# duckypad.net
KiCad netlist of a schematic drawn in EAGLE
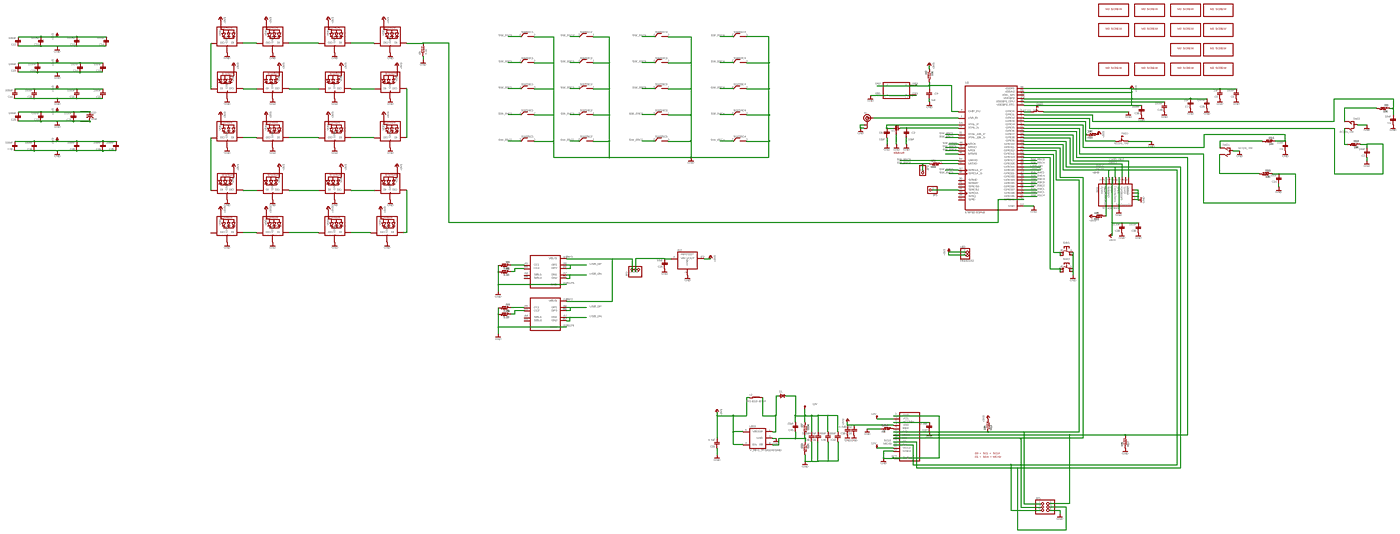
[diagram p0: schematic, sheet 1, overview]
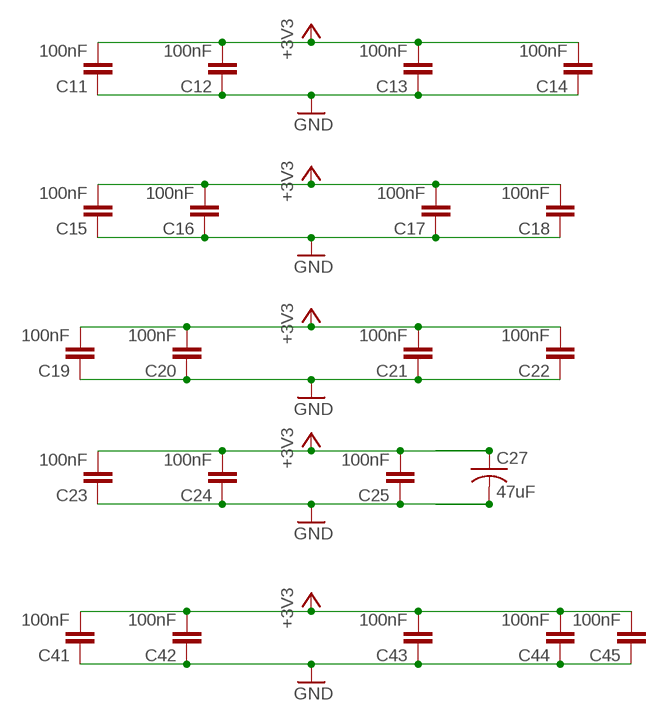
[diagram p1: schematic, sheet 1, part 1 of 4]
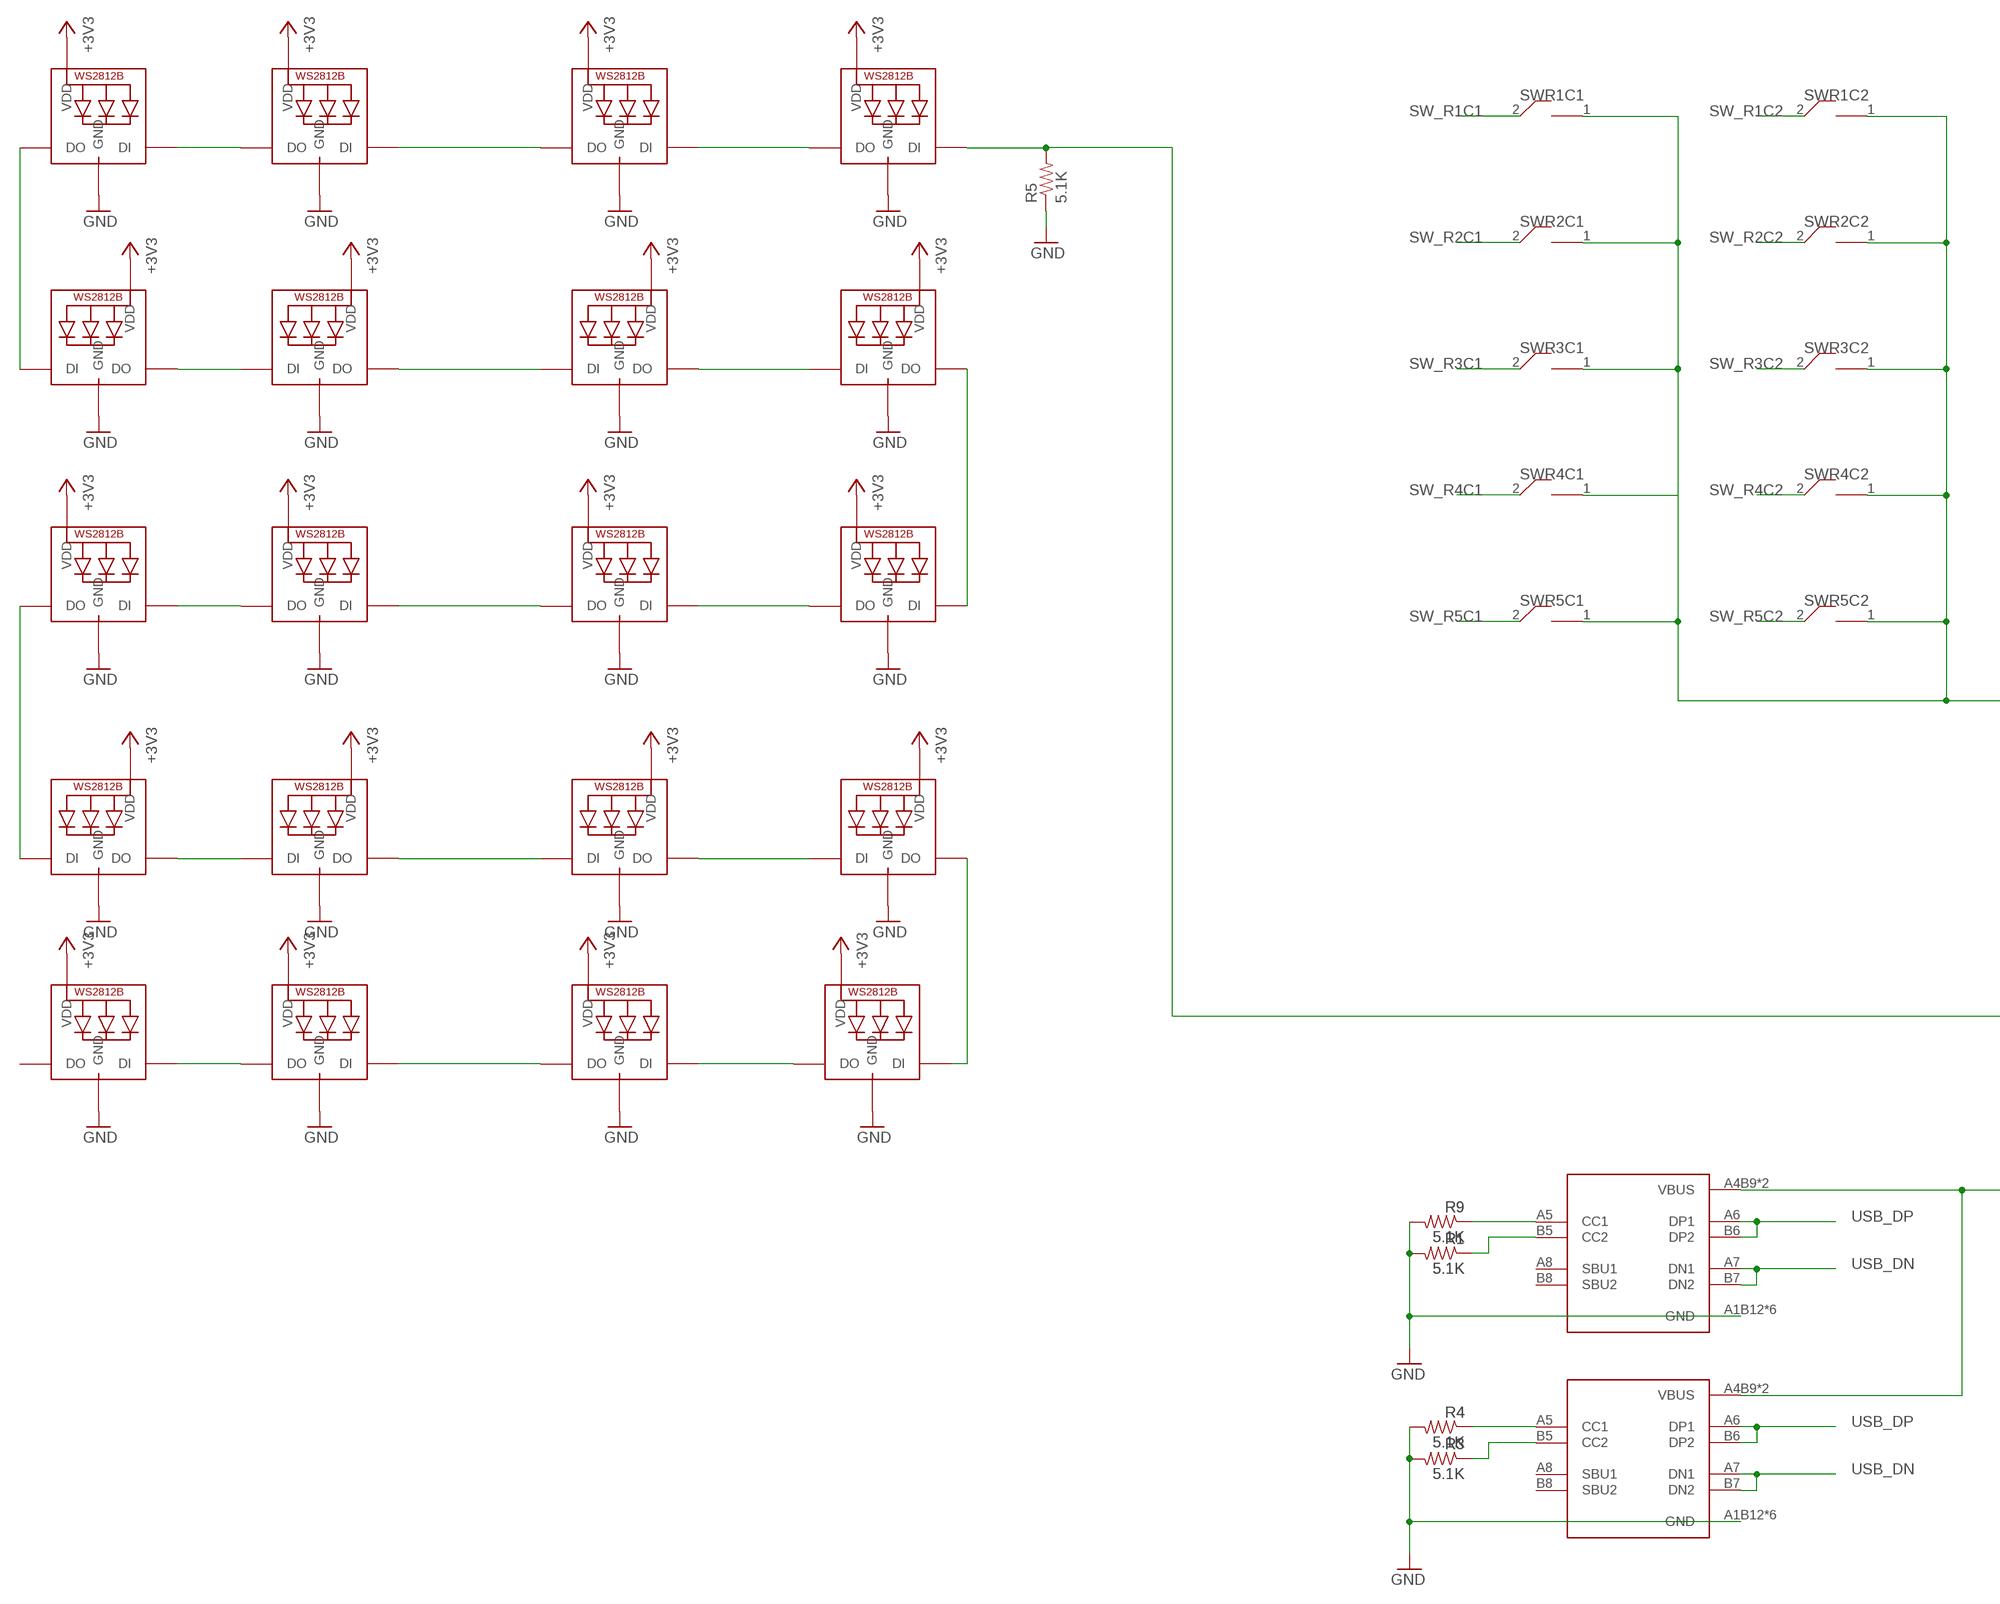
[diagram p2: schematic, sheet 1, part 2 of 4]
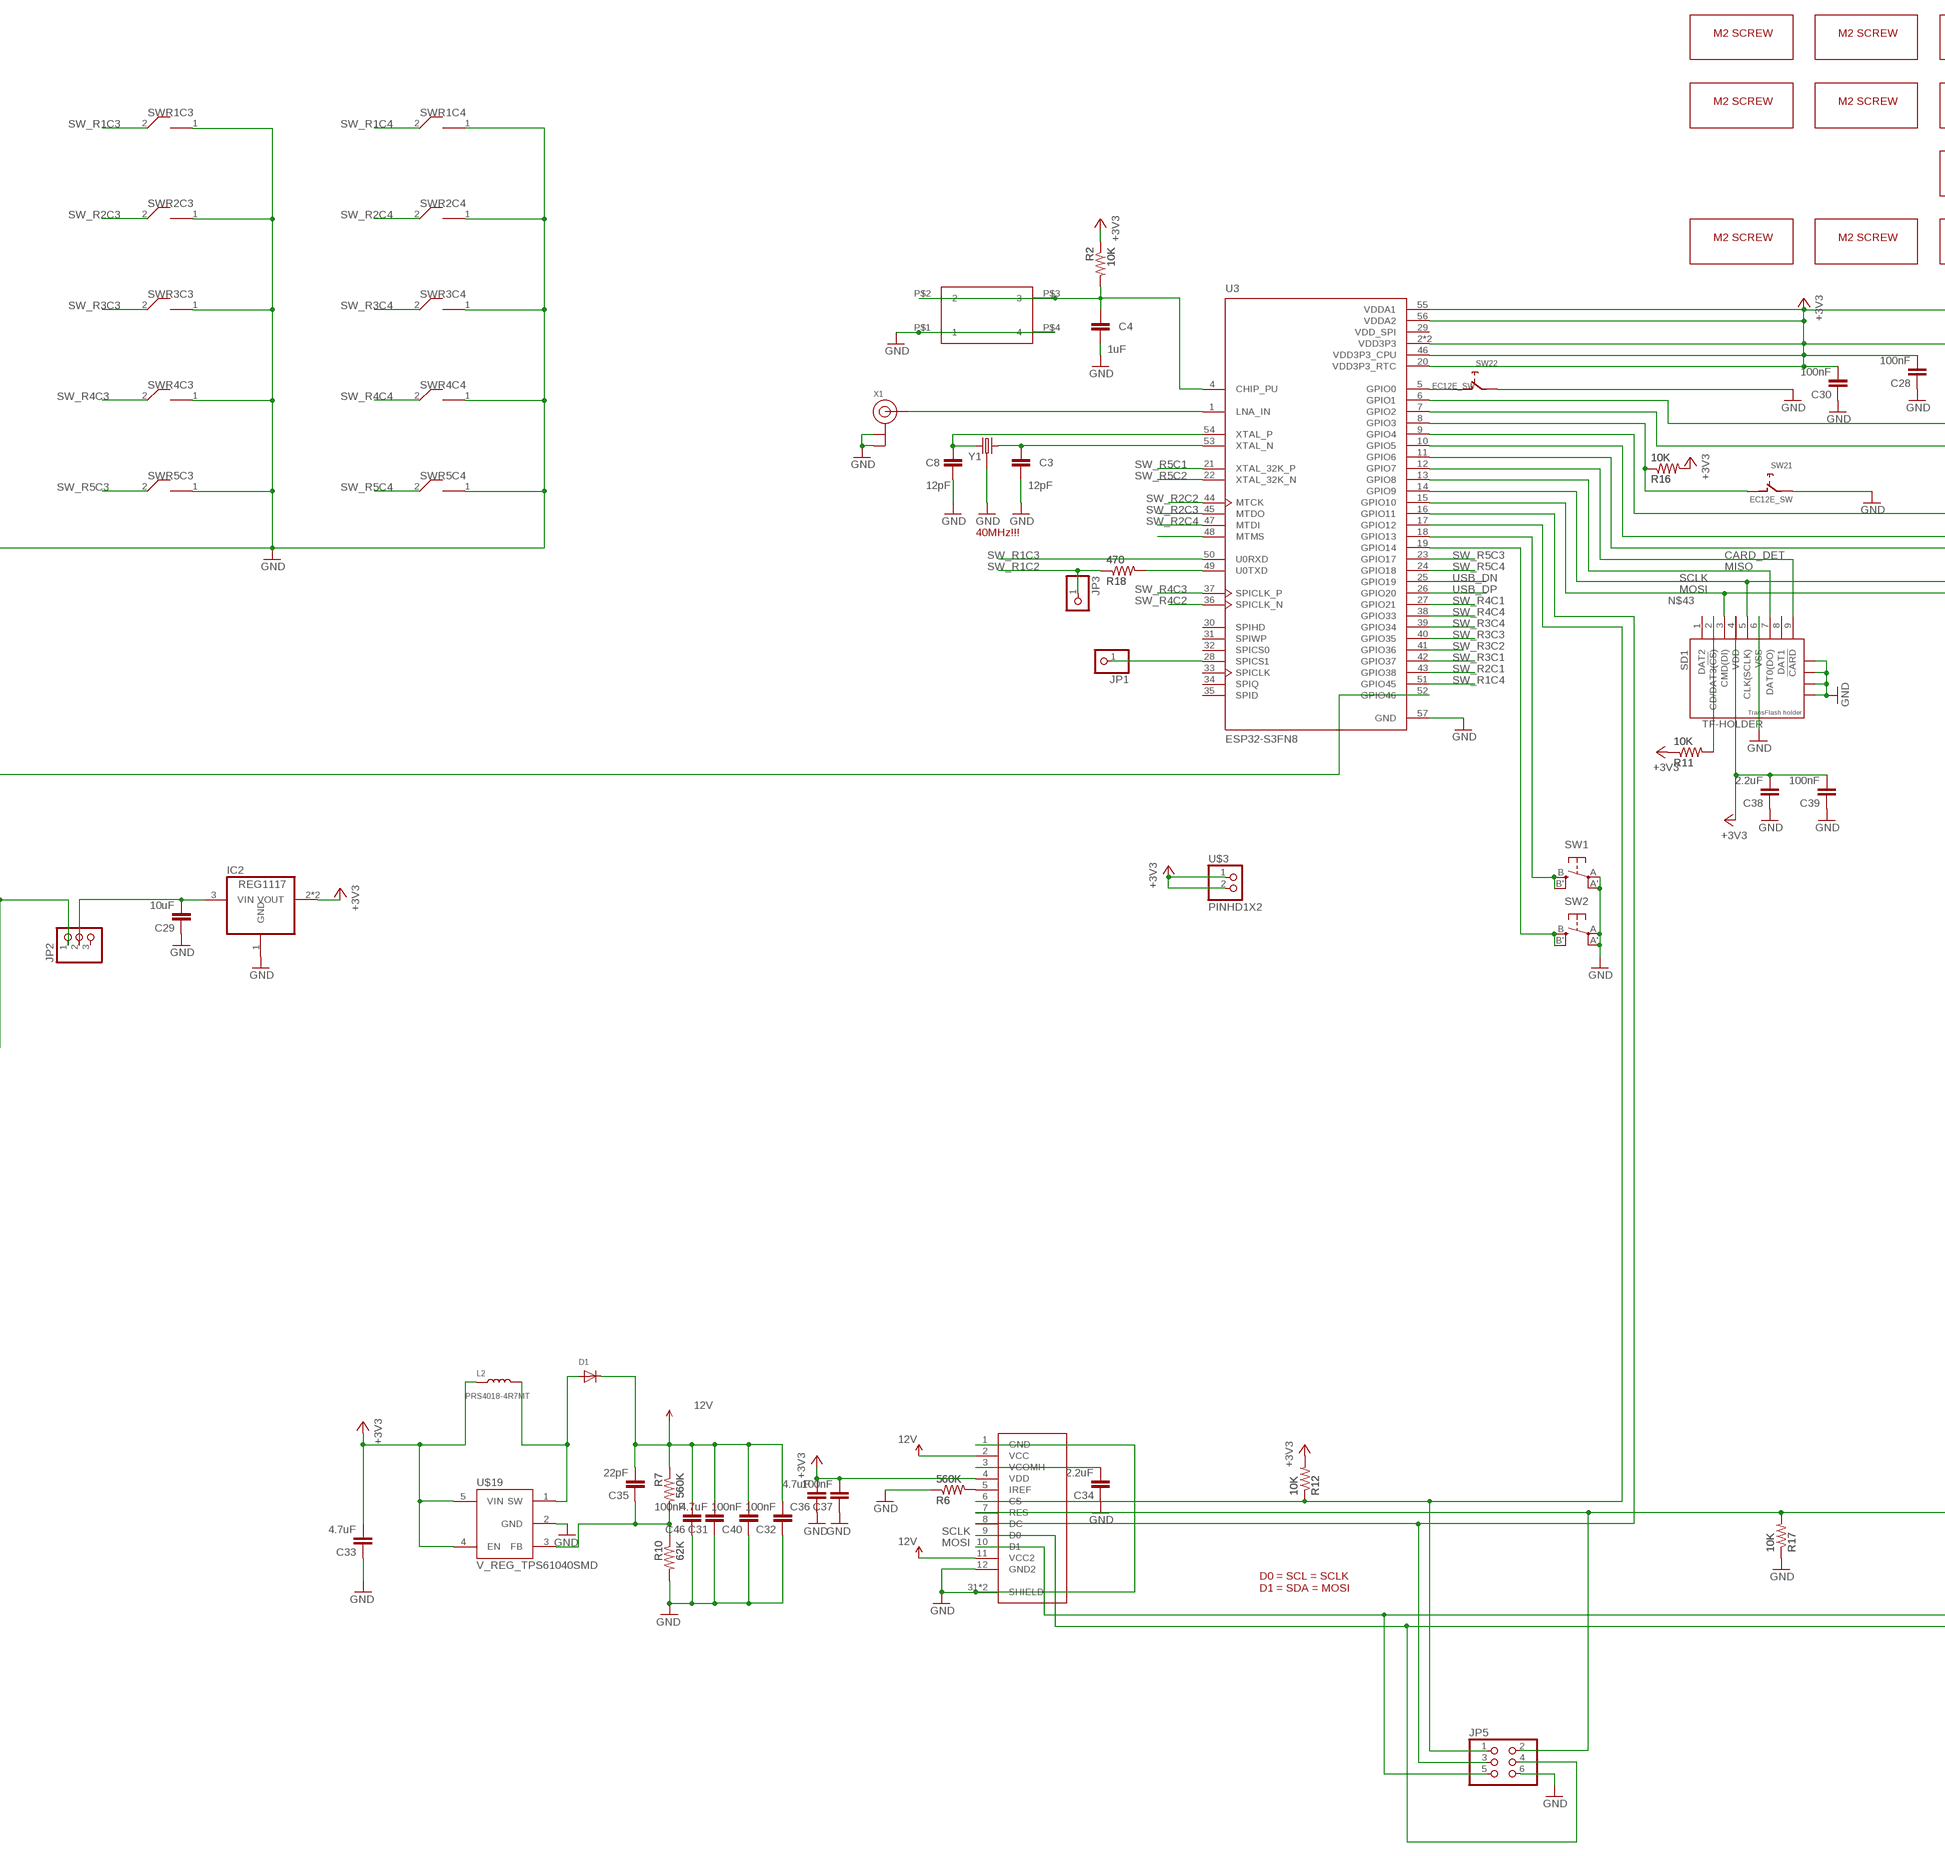
[diagram p3: schematic, sheet 1, part 3 of 4]
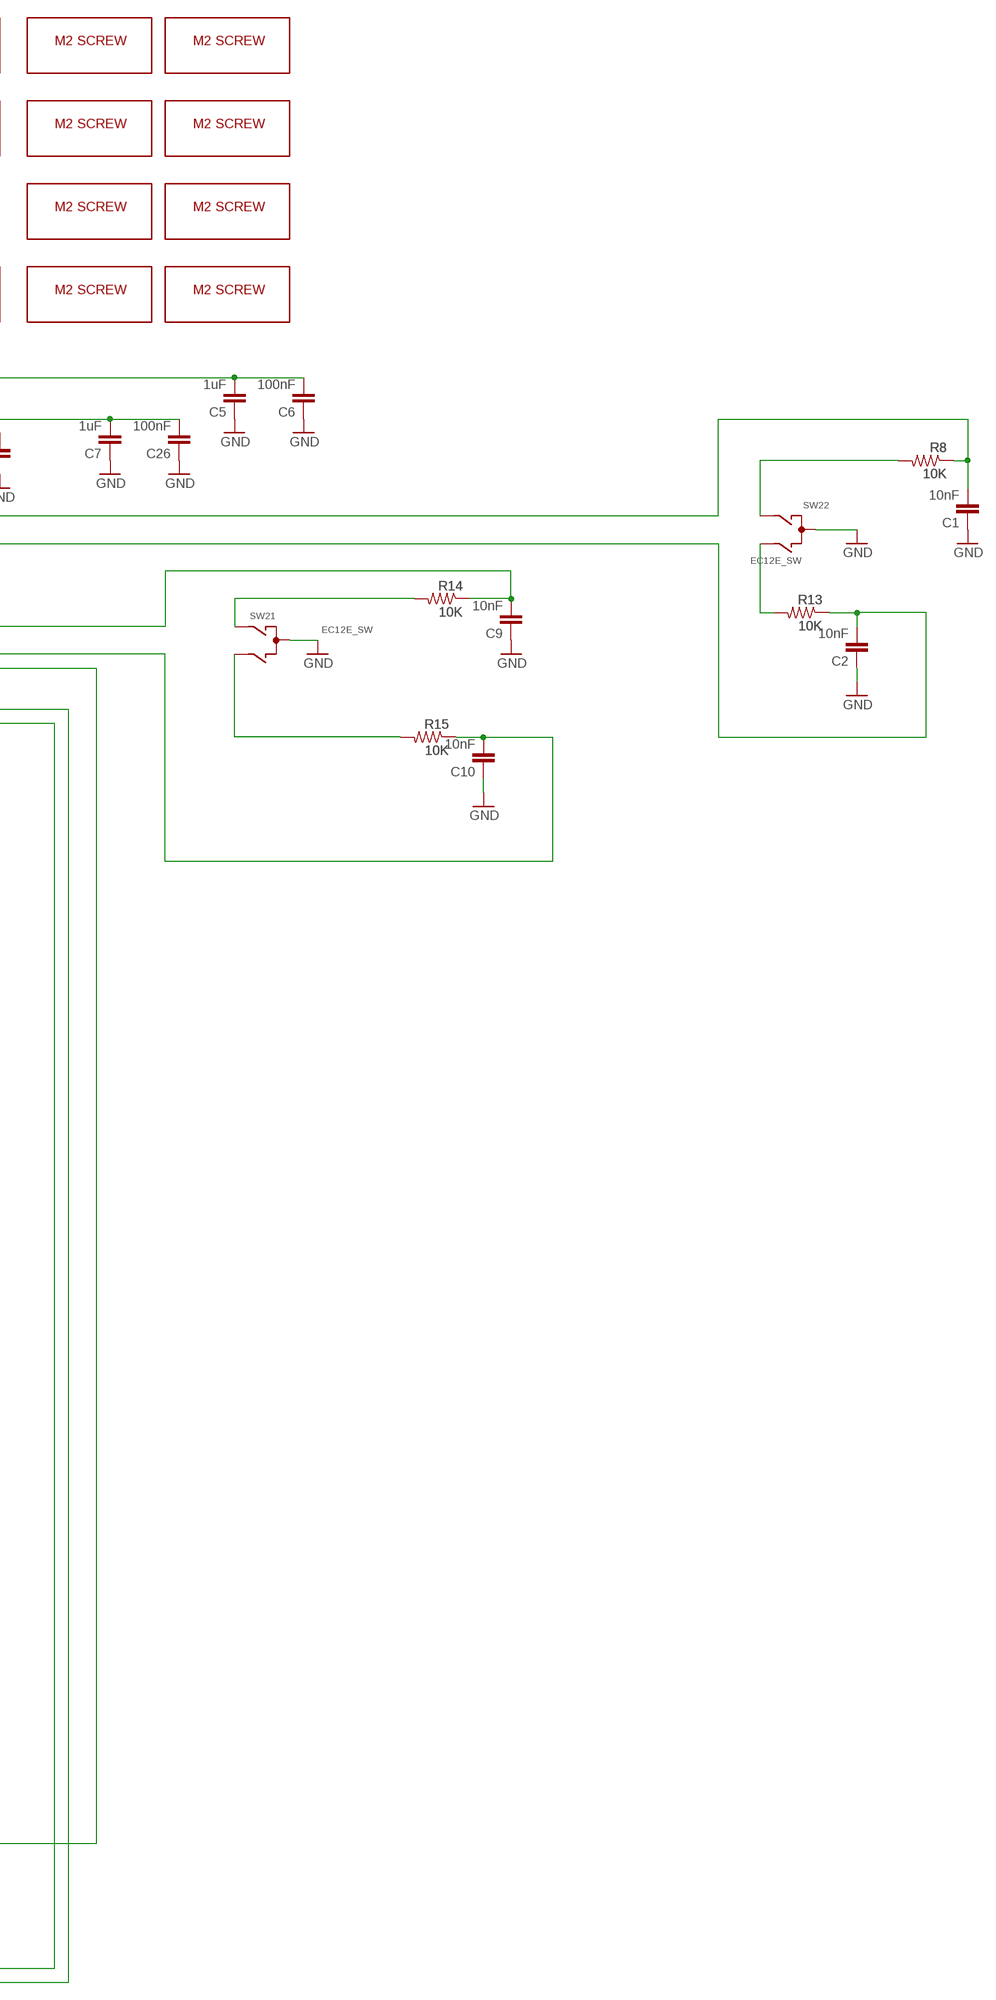
[diagram p4: schematic, sheet 1, part 4 of 4]

(export (version "E")
  (design (tool "Eeschema 10.0.6"))
  (components
    (comp (ref "C1")
      (value "10nF")
      (footprint "eagle-import:0805")
      (libsource (lib "eagle-import") (part "CAP0805"))
    )
    (comp (ref "C2")
      (value "10nF")
      (footprint "eagle-import:0805")
      (libsource (lib "eagle-import") (part "CAP0805"))
    )
    (comp (ref "C3")
      (value "12pF")
      (footprint "eagle-import:0805")
      (libsource (lib "eagle-import") (part "CAP0805"))
    )
    (comp (ref "C4")
      (value "1uF")
      (footprint "eagle-import:0805")
      (libsource (lib "eagle-import") (part "CAP0805"))
    )
    (comp (ref "C5")
      (value "1uF")
      (footprint "eagle-import:0805")
      (libsource (lib "eagle-import") (part "CAP0805"))
    )
    (comp (ref "C6")
      (value "100nF")
      (footprint "eagle-import:0805")
      (libsource (lib "eagle-import") (part "CAP0805"))
    )
    (comp (ref "C7")
      (value "1uF")
      (footprint "eagle-import:0805")
      (libsource (lib "eagle-import") (part "CAP0805"))
    )
    (comp (ref "C8")
      (value "12pF")
      (footprint "eagle-import:0805")
      (libsource (lib "eagle-import") (part "CAP0805"))
    )
    (comp (ref "C9")
      (value "10nF")
      (footprint "eagle-import:0805")
      (libsource (lib "eagle-import") (part "CAP0805"))
    )
    (comp (ref "C10")
      (value "10nF")
      (footprint "eagle-import:0805")
      (libsource (lib "eagle-import") (part "CAP0805"))
    )
    (comp (ref "C11")
      (value "100nF")
      (footprint "eagle-import:0805")
      (libsource (lib "eagle-import") (part "CAP0805"))
    )
    (comp (ref "C12")
      (value "100nF")
      (footprint "eagle-import:0805")
      (libsource (lib "eagle-import") (part "CAP0805"))
    )
    (comp (ref "C13")
      (value "100nF")
      (footprint "eagle-import:0805")
      (libsource (lib "eagle-import") (part "CAP0805"))
    )
    (comp (ref "C14")
      (value "100nF")
      (footprint "eagle-import:0805")
      (libsource (lib "eagle-import") (part "CAP0805"))
    )
    (comp (ref "C15")
      (value "100nF")
      (footprint "eagle-import:0805")
      (libsource (lib "eagle-import") (part "CAP0805"))
    )
    (comp (ref "C16")
      (value "100nF")
      (footprint "eagle-import:0805")
      (libsource (lib "eagle-import") (part "CAP0805"))
    )
    (comp (ref "C17")
      (value "100nF")
      (footprint "eagle-import:0805")
      (libsource (lib "eagle-import") (part "CAP0805"))
    )
    (comp (ref "C18")
      (value "100nF")
      (footprint "eagle-import:0805")
      (libsource (lib "eagle-import") (part "CAP0805"))
    )
    (comp (ref "C19")
      (value "100nF")
      (footprint "eagle-import:0805")
      (libsource (lib "eagle-import") (part "CAP0805"))
    )
    (comp (ref "C20")
      (value "100nF")
      (footprint "eagle-import:0805")
      (libsource (lib "eagle-import") (part "CAP0805"))
    )
    (comp (ref "C21")
      (value "100nF")
      (footprint "eagle-import:0805")
      (libsource (lib "eagle-import") (part "CAP0805"))
    )
    (comp (ref "C22")
      (value "100nF")
      (footprint "eagle-import:0805")
      (libsource (lib "eagle-import") (part "CAP0805"))
    )
    (comp (ref "C23")
      (value "100nF")
      (footprint "eagle-import:0805")
      (libsource (lib "eagle-import") (part "CAP0805"))
    )
    (comp (ref "C24")
      (value "100nF")
      (footprint "eagle-import:0805")
      (libsource (lib "eagle-import") (part "CAP0805"))
    )
    (comp (ref "C25")
      (value "100nF")
      (footprint "eagle-import:0805")
      (libsource (lib "eagle-import") (part "CAP0805"))
    )
    (comp (ref "C26")
      (value "100nF")
      (footprint "eagle-import:0805")
      (libsource (lib "eagle-import") (part "CAP0805"))
    )
    (comp (ref "C27")
      (value "47uF")
      (footprint "eagle-import:C1210")
      (libsource (lib "eagle-import") (part "C-USC1210"))
    )
    (comp (ref "C28")
      (value "100nF")
      (footprint "eagle-import:0805")
      (libsource (lib "eagle-import") (part "CAP0805"))
    )
    (comp (ref "C29")
      (value "10uF")
      (footprint "eagle-import:0805")
      (libsource (lib "eagle-import") (part "CAP0805"))
    )
    (comp (ref "C30")
      (value "100nF")
      (footprint "eagle-import:0805")
      (libsource (lib "eagle-import") (part "CAP0805"))
    )
    (comp (ref "C31")
      (value "4.7uF")
      (footprint "eagle-import:0805")
      (libsource (lib "eagle-import") (part "CAP0805"))
    )
    (comp (ref "C32")
      (value "100nF")
      (footprint "eagle-import:0805")
      (libsource (lib "eagle-import") (part "CAP0805"))
    )
    (comp (ref "C33")
      (value "4.7uF")
      (footprint "eagle-import:0805")
      (libsource (lib "eagle-import") (part "CAP0805"))
    )
    (comp (ref "C34")
      (value "2.2uF")
      (footprint "eagle-import:0805")
      (libsource (lib "eagle-import") (part "CAP0805"))
    )
    (comp (ref "C35")
      (value "22pF")
      (footprint "eagle-import:0805")
      (libsource (lib "eagle-import") (part "CAP0805"))
    )
    (comp (ref "C36")
      (value "4.7uF")
      (footprint "eagle-import:0805")
      (libsource (lib "eagle-import") (part "CAP0805"))
    )
    (comp (ref "C37")
      (value "100nF")
      (footprint "eagle-import:0805")
      (libsource (lib "eagle-import") (part "CAP0805"))
    )
    (comp (ref "C38")
      (value "2.2uF")
      (footprint "eagle-import:0805")
      (libsource (lib "eagle-import") (part "CAP0805"))
    )
    (comp (ref "C39")
      (value "100nF")
      (footprint "eagle-import:0805")
      (libsource (lib "eagle-import") (part "CAP0805"))
    )
    (comp (ref "C40")
      (value "100nF")
      (footprint "eagle-import:0805")
      (libsource (lib "eagle-import") (part "CAP0805"))
    )
    (comp (ref "C41")
      (value "100nF")
      (footprint "eagle-import:0805")
      (libsource (lib "eagle-import") (part "CAP0805"))
    )
    (comp (ref "C42")
      (value "100nF")
      (footprint "eagle-import:0805")
      (libsource (lib "eagle-import") (part "CAP0805"))
    )
    (comp (ref "C43")
      (value "100nF")
      (footprint "eagle-import:0805")
      (libsource (lib "eagle-import") (part "CAP0805"))
    )
    (comp (ref "C44")
      (value "100nF")
      (footprint "eagle-import:0805")
      (libsource (lib "eagle-import") (part "CAP0805"))
    )
    (comp (ref "C45")
      (value "100nF")
      (footprint "eagle-import:0805")
      (libsource (lib "eagle-import") (part "CAP0805"))
    )
    (comp (ref "C46")
      (value "100nF")
      (footprint "eagle-import:0805")
      (libsource (lib "eagle-import") (part "CAP0805"))
    )
    (comp (ref "D1")
      (value "DIODESOD-123")
      (footprint "eagle-import:SOD-123")
      (libsource (lib "eagle-import") (part "DIODESOD-123"))
    )
    (comp (ref "IC2")
      (value "REG1117")
      (footprint "eagle-import:SOT223")
      (libsource (lib "eagle-import") (part "REG1117"))
    )
    (comp (ref "JP1")
      (value "PINHD-1X1CB")
      (footprint "eagle-import:1X01-CLEANBIG")
      (libsource (lib "eagle-import") (part "PINHD-1X1CB"))
    )
    (comp (ref "JP2")
      (value "PINHD-1X3CB")
      (footprint "eagle-import:1X03-CLEANBIG")
      (libsource (lib "eagle-import") (part "PINHD-1X3CB"))
    )
    (comp (ref "JP3")
      (value "PINHD-1X1CB")
      (footprint "eagle-import:1X01-CLEANBIG")
      (libsource (lib "eagle-import") (part "PINHD-1X1CB"))
    )
    (comp (ref "JP5")
      (value "PINHD-2X3")
      (footprint "eagle-import:2X03")
      (libsource (lib "eagle-import") (part "PINHD-2X3"))
    )
    (comp (ref "L2")
      (value "PRS4018-4R7MT")
      (footprint "eagle-import:L4030")
      (libsource (lib "eagle-import") (part "L-4030"))
    )
    (comp (ref "LED_R1C1")
      (value "WS2812B")
      (footprint "eagle-import:REVERSE_MNT")
      (libsource (lib "eagle-import") (part "WS2812B"))
    )
    (comp (ref "LED_R1C2")
      (value "WS2812B")
      (footprint "eagle-import:REVERSE_MNT")
      (libsource (lib "eagle-import") (part "WS2812B"))
    )
    (comp (ref "LED_R1C3")
      (value "WS2812B")
      (footprint "eagle-import:REVERSE_MNT")
      (libsource (lib "eagle-import") (part "WS2812B"))
    )
    (comp (ref "LED_R1C4")
      (value "WS2812B")
      (footprint "eagle-import:REVERSE_MNT")
      (libsource (lib "eagle-import") (part "WS2812B"))
    )
    (comp (ref "LED_R2C1")
      (value "WS2812B")
      (footprint "eagle-import:REVERSE_MNT")
      (libsource (lib "eagle-import") (part "WS2812B"))
    )
    (comp (ref "LED_R2C2")
      (value "WS2812B")
      (footprint "eagle-import:REVERSE_MNT")
      (libsource (lib "eagle-import") (part "WS2812B"))
    )
    (comp (ref "LED_R2C3")
      (value "WS2812B")
      (footprint "eagle-import:REVERSE_MNT")
      (libsource (lib "eagle-import") (part "WS2812B"))
    )
    (comp (ref "LED_R2C4")
      (value "WS2812B")
      (footprint "eagle-import:REVERSE_MNT")
      (libsource (lib "eagle-import") (part "WS2812B"))
    )
    (comp (ref "LED_R3C1")
      (value "WS2812B")
      (footprint "eagle-import:REVERSE_MNT")
      (libsource (lib "eagle-import") (part "WS2812B"))
    )
    (comp (ref "LED_R3C2")
      (value "WS2812B")
      (footprint "eagle-import:REVERSE_MNT")
      (libsource (lib "eagle-import") (part "WS2812B"))
    )
    (comp (ref "LED_R3C3")
      (value "WS2812B")
      (footprint "eagle-import:REVERSE_MNT")
      (libsource (lib "eagle-import") (part "WS2812B"))
    )
    (comp (ref "LED_R3C4")
      (value "WS2812B")
      (footprint "eagle-import:REVERSE_MNT")
      (libsource (lib "eagle-import") (part "WS2812B"))
    )
    (comp (ref "LED_R4C1")
      (value "WS2812B")
      (footprint "eagle-import:REVERSE_MNT")
      (libsource (lib "eagle-import") (part "WS2812B"))
    )
    (comp (ref "LED_R4C2")
      (value "WS2812B")
      (footprint "eagle-import:REVERSE_MNT")
      (libsource (lib "eagle-import") (part "WS2812B"))
    )
    (comp (ref "LED_R4C3")
      (value "WS2812B")
      (footprint "eagle-import:REVERSE_MNT")
      (libsource (lib "eagle-import") (part "WS2812B"))
    )
    (comp (ref "LED_R4C4")
      (value "WS2812B")
      (footprint "eagle-import:REVERSE_MNT")
      (libsource (lib "eagle-import") (part "WS2812B"))
    )
    (comp (ref "LED_R5C1")
      (value "WS2812B")
      (footprint "eagle-import:REVERSE_MNT")
      (libsource (lib "eagle-import") (part "WS2812B"))
    )
    (comp (ref "LED_R5C2")
      (value "WS2812B")
      (footprint "eagle-import:REVERSE_MNT")
      (libsource (lib "eagle-import") (part "WS2812B"))
    )
    (comp (ref "LED_R5C3")
      (value "WS2812B")
      (footprint "eagle-import:REVERSE_MNT")
      (libsource (lib "eagle-import") (part "WS2812B"))
    )
    (comp (ref "LED_R5C4")
      (value "WS2812B")
      (footprint "eagle-import:REVERSE_MNT")
      (libsource (lib "eagle-import") (part "WS2812B"))
    )
    (comp (ref "R1")
      (value "5.1K")
      (footprint "eagle-import:0805")
      (libsource (lib "eagle-import") (part "joyAnalog_RESISTOR0805-RES"))
    )
    (comp (ref "R2")
      (value "10K")
      (footprint "eagle-import:0805")
      (libsource (lib "eagle-import") (part "joyAnalog_RESISTOR0805-RES"))
    )
    (comp (ref "R3")
      (value "5.1K")
      (footprint "eagle-import:0805")
      (libsource (lib "eagle-import") (part "joyAnalog_RESISTOR0805-RES"))
    )
    (comp (ref "R4")
      (value "5.1K")
      (footprint "eagle-import:0805")
      (libsource (lib "eagle-import") (part "joyAnalog_RESISTOR0805-RES"))
    )
    (comp (ref "R5")
      (value "5.1K")
      (footprint "eagle-import:0805")
      (libsource (lib "eagle-import") (part "RESISTOR0805-RES"))
    )
    (comp (ref "R6")
      (value "560K")
      (footprint "eagle-import:0805")
      (libsource (lib "eagle-import") (part "joyAnalog_RESISTOR0805-RES"))
    )
    (comp (ref "R7")
      (value "560K")
      (footprint "eagle-import:0805")
      (libsource (lib "eagle-import") (part "joyAnalog_RESISTOR0805-RES"))
    )
    (comp (ref "R8")
      (value "10K")
      (footprint "eagle-import:0805")
      (libsource (lib "eagle-import") (part "joyAnalog_RESISTOR0805-RES"))
    )
    (comp (ref "R9")
      (value "5.1K")
      (footprint "eagle-import:0805")
      (libsource (lib "eagle-import") (part "joyAnalog_RESISTOR0805-RES"))
    )
    (comp (ref "R10")
      (value "62K")
      (footprint "eagle-import:0805")
      (libsource (lib "eagle-import") (part "joyAnalog_RESISTOR0805-RES"))
    )
    (comp (ref "R11")
      (value "10K")
      (footprint "eagle-import:0805")
      (libsource (lib "eagle-import") (part "joyAnalog_RESISTOR0805-RES"))
    )
    (comp (ref "R12")
      (value "10K")
      (footprint "eagle-import:0805")
      (libsource (lib "eagle-import") (part "joyAnalog_RESISTOR0805-RES"))
    )
    (comp (ref "R13")
      (value "10K")
      (footprint "eagle-import:0805")
      (libsource (lib "eagle-import") (part "joyAnalog_RESISTOR0805-RES"))
    )
    (comp (ref "R14")
      (value "10K")
      (footprint "eagle-import:0805")
      (libsource (lib "eagle-import") (part "joyAnalog_RESISTOR0805-RES"))
    )
    (comp (ref "R15")
      (value "10K")
      (footprint "eagle-import:0805")
      (libsource (lib "eagle-import") (part "joyAnalog_RESISTOR0805-RES"))
    )
    (comp (ref "R16")
      (value "10K")
      (footprint "eagle-import:0805")
      (libsource (lib "eagle-import") (part "joyAnalog_RESISTOR0805-RES"))
    )
    (comp (ref "R17")
      (value "10K")
      (footprint "eagle-import:0805")
      (libsource (lib "eagle-import") (part "joyAnalog_RESISTOR0805-RES"))
    )
    (comp (ref "R18")
      (value "470")
      (footprint "eagle-import:0805")
      (libsource (lib "eagle-import") (part "joyAnalog_RESISTOR0805-RES"))
    )
    (comp (ref "SD1")
      (value "TF-HOLDER")
      (footprint "eagle-import:TF-PULL")
      (libsource (lib "eagle-import") (part "TF-HOLDER"))
    )
    (comp (ref "SW1")
      (value "SPST_TACT-EVQQ2")
      (footprint "eagle-import:EVQ-Q2")
      (libsource (lib "eagle-import") (part "SPST_TACT-EVQQ2"))
    )
    (comp (ref "SW2")
      (value "SPST_TACT-EVQQ2")
      (footprint "eagle-import:EVQ-Q2")
      (libsource (lib "eagle-import") (part "SPST_TACT-EVQQ2"))
    )
    (comp (ref "SW3")
      (value "324_SW324_SWITCH_FOOT_HOLE")
      (footprint "eagle-import:342_SWICH_FOOT_HOLE")
      (libsource (lib "eagle-import") (part "324_SW324_SWITCH_FOOT_HOLE"))
    )
    (comp (ref "SW21")
      (value "EC12E_SW")
      (footprint "eagle-import:ALPS_EC12E_SW")
      (fields (field (name "MPN") "EC12E2424407"))
      (libsource (lib "eagle-import") (part "EC12E_SW"))
    )
    (comp (ref "SW22")
      (value "EC12E_SW")
      (footprint "eagle-import:ALPS_EC12E_SW")
      (fields (field (name "MPN") "EC12E2424407"))
      (libsource (lib "eagle-import") (part "EC12E_SW"))
    )
    (comp (ref "SWR1C1")
      (value "KAILH_SWITCH_SOCKET_KAILH_SWITCH_SOCKET")
      (footprint "eagle-import:KAILH_SWITCH_SOCKET_SWITCH_SOCKET")
      (libsource (lib "eagle-import") (part "KAILH_SWITCH_SOCKET_KAILH_SWITCH_SOCKET"))
    )
    (comp (ref "SWR1C2")
      (value "KAILH_SWITCH_SOCKET_KAILH_SWITCH_SOCKET")
      (footprint "eagle-import:KAILH_SWITCH_SOCKET_SWITCH_SOCKET")
      (libsource (lib "eagle-import") (part "KAILH_SWITCH_SOCKET_KAILH_SWITCH_SOCKET"))
    )
    (comp (ref "SWR1C3")
      (value "KAILH_SWITCH_SOCKET_KAILH_SWITCH_SOCKET")
      (footprint "eagle-import:KAILH_SWITCH_SOCKET_SWITCH_SOCKET")
      (libsource (lib "eagle-import") (part "KAILH_SWITCH_SOCKET_KAILH_SWITCH_SOCKET"))
    )
    (comp (ref "SWR1C4")
      (value "KAILH_SWITCH_SOCKET_KAILH_SWITCH_SOCKET")
      (footprint "eagle-import:KAILH_SWITCH_SOCKET_SWITCH_SOCKET")
      (libsource (lib "eagle-import") (part "KAILH_SWITCH_SOCKET_KAILH_SWITCH_SOCKET"))
    )
    (comp (ref "SWR2C1")
      (value "KAILH_SWITCH_SOCKET_KAILH_SWITCH_SOCKET")
      (footprint "eagle-import:KAILH_SWITCH_SOCKET_SWITCH_SOCKET")
      (libsource (lib "eagle-import") (part "KAILH_SWITCH_SOCKET_KAILH_SWITCH_SOCKET"))
    )
    (comp (ref "SWR2C2")
      (value "KAILH_SWITCH_SOCKET_KAILH_SWITCH_SOCKET")
      (footprint "eagle-import:KAILH_SWITCH_SOCKET_SWITCH_SOCKET")
      (libsource (lib "eagle-import") (part "KAILH_SWITCH_SOCKET_KAILH_SWITCH_SOCKET"))
    )
    (comp (ref "SWR2C3")
      (value "KAILH_SWITCH_SOCKET_KAILH_SWITCH_SOCKET")
      (footprint "eagle-import:KAILH_SWITCH_SOCKET_SWITCH_SOCKET")
      (libsource (lib "eagle-import") (part "KAILH_SWITCH_SOCKET_KAILH_SWITCH_SOCKET"))
    )
    (comp (ref "SWR2C4")
      (value "KAILH_SWITCH_SOCKET_KAILH_SWITCH_SOCKET")
      (footprint "eagle-import:KAILH_SWITCH_SOCKET_SWITCH_SOCKET")
      (libsource (lib "eagle-import") (part "KAILH_SWITCH_SOCKET_KAILH_SWITCH_SOCKET"))
    )
    (comp (ref "SWR3C1")
      (value "KAILH_SWITCH_SOCKET_KAILH_SWITCH_SOCKET")
      (footprint "eagle-import:KAILH_SWITCH_SOCKET_SWITCH_SOCKET")
      (libsource (lib "eagle-import") (part "KAILH_SWITCH_SOCKET_KAILH_SWITCH_SOCKET"))
    )
    (comp (ref "SWR3C2")
      (value "KAILH_SWITCH_SOCKET_KAILH_SWITCH_SOCKET")
      (footprint "eagle-import:KAILH_SWITCH_SOCKET_SWITCH_SOCKET")
      (libsource (lib "eagle-import") (part "KAILH_SWITCH_SOCKET_KAILH_SWITCH_SOCKET"))
    )
    (comp (ref "SWR3C3")
      (value "KAILH_SWITCH_SOCKET_KAILH_SWITCH_SOCKET")
      (footprint "eagle-import:KAILH_SWITCH_SOCKET_SWITCH_SOCKET")
      (libsource (lib "eagle-import") (part "KAILH_SWITCH_SOCKET_KAILH_SWITCH_SOCKET"))
    )
    (comp (ref "SWR3C4")
      (value "KAILH_SWITCH_SOCKET_KAILH_SWITCH_SOCKET")
      (footprint "eagle-import:KAILH_SWITCH_SOCKET_SWITCH_SOCKET")
      (libsource (lib "eagle-import") (part "KAILH_SWITCH_SOCKET_KAILH_SWITCH_SOCKET"))
    )
    (comp (ref "SWR4C1")
      (value "KAILH_SWITCH_SOCKET_KAILH_SWITCH_SOCKET")
      (footprint "eagle-import:KAILH_SWITCH_SOCKET_SWITCH_SOCKET")
      (libsource (lib "eagle-import") (part "KAILH_SWITCH_SOCKET_KAILH_SWITCH_SOCKET"))
    )
    (comp (ref "SWR4C2")
      (value "KAILH_SWITCH_SOCKET_KAILH_SWITCH_SOCKET")
      (footprint "eagle-import:KAILH_SWITCH_SOCKET_SWITCH_SOCKET")
      (libsource (lib "eagle-import") (part "KAILH_SWITCH_SOCKET_KAILH_SWITCH_SOCKET"))
    )
    (comp (ref "SWR4C3")
      (value "KAILH_SWITCH_SOCKET_KAILH_SWITCH_SOCKET")
      (footprint "eagle-import:KAILH_SWITCH_SOCKET_SWITCH_SOCKET")
      (libsource (lib "eagle-import") (part "KAILH_SWITCH_SOCKET_KAILH_SWITCH_SOCKET"))
    )
    (comp (ref "SWR4C4")
      (value "KAILH_SWITCH_SOCKET_KAILH_SWITCH_SOCKET")
      (footprint "eagle-import:KAILH_SWITCH_SOCKET_SWITCH_SOCKET")
      (libsource (lib "eagle-import") (part "KAILH_SWITCH_SOCKET_KAILH_SWITCH_SOCKET"))
    )
    (comp (ref "SWR5C1")
      (value "KAILH_SWITCH_SOCKET_KAILH_SWITCH_SOCKET")
      (footprint "eagle-import:KAILH_SWITCH_SOCKET_SWITCH_SOCKET")
      (libsource (lib "eagle-import") (part "KAILH_SWITCH_SOCKET_KAILH_SWITCH_SOCKET"))
    )
    (comp (ref "SWR5C2")
      (value "KAILH_SWITCH_SOCKET_KAILH_SWITCH_SOCKET")
      (footprint "eagle-import:KAILH_SWITCH_SOCKET_SWITCH_SOCKET")
      (libsource (lib "eagle-import") (part "KAILH_SWITCH_SOCKET_KAILH_SWITCH_SOCKET"))
    )
    (comp (ref "SWR5C3")
      (value "KAILH_SWITCH_SOCKET_KAILH_SWITCH_SOCKET")
      (footprint "eagle-import:KAILH_SWITCH_SOCKET_SWITCH_SOCKET")
      (libsource (lib "eagle-import") (part "KAILH_SWITCH_SOCKET_KAILH_SWITCH_SOCKET"))
    )
    (comp (ref "SWR5C4")
      (value "KAILH_SWITCH_SOCKET_KAILH_SWITCH_SOCKET")
      (footprint "eagle-import:KAILH_SWITCH_SOCKET_SWITCH_SOCKET")
      (libsource (lib "eagle-import") (part "KAILH_SWITCH_SOCKET_KAILH_SWITCH_SOCKET"))
    )
    (comp (ref "U$2")
      (value "OLED128")
      (footprint "eagle-import:LUL_UG-2864HSWEG01_1.3_WRAPAROUND")
      (libsource (lib "eagle-import") (part "OLED128"))
    )
    (comp (ref "U$3")
      (value "PINHD1X2")
      (footprint "eagle-import:1X02")
      (libsource (lib "eagle-import") (part "PINHD1X2"))
    )
    (comp (ref "U$7")
      (value "M2_SCREW_DEV")
      (footprint "eagle-import:M2_SCREW_FOOT")
      (libsource (lib "eagle-import") (part "M2_SCREW_DEV"))
    )
    (comp (ref "U$8")
      (value "M2_SCREW_DEV")
      (footprint "eagle-import:M2_SCREW_FOOT")
      (libsource (lib "eagle-import") (part "M2_SCREW_DEV"))
    )
    (comp (ref "U$9")
      (value "M2_SCREW_DEV")
      (footprint "eagle-import:M2_SCREW_FOOT")
      (libsource (lib "eagle-import") (part "M2_SCREW_DEV"))
    )
    (comp (ref "U$10")
      (value "M2_SCREW_DEV")
      (footprint "eagle-import:M2_SCREW_FOOT")
      (libsource (lib "eagle-import") (part "M2_SCREW_DEV"))
    )
    (comp (ref "U$11")
      (value "M2_SCREW_DEV")
      (footprint "eagle-import:M2_SCREW_FOOT")
      (libsource (lib "eagle-import") (part "M2_SCREW_DEV"))
    )
    (comp (ref "U$12")
      (value "M2_SCREW_DEV")
      (footprint "eagle-import:M2_SCREW_FOOT")
      (libsource (lib "eagle-import") (part "M2_SCREW_DEV"))
    )
    (comp (ref "U$13")
      (value "M2_SCREW_DEV")
      (footprint "eagle-import:M2_SCREW_FOOT")
      (libsource (lib "eagle-import") (part "M2_SCREW_DEV"))
    )
    (comp (ref "U$14")
      (value "M2_SCREW_DEV")
      (footprint "eagle-import:M2_SCREW_FOOT")
      (libsource (lib "eagle-import") (part "M2_SCREW_DEV"))
    )
    (comp (ref "U$15")
      (value "M2_SCREW_DEV")
      (footprint "eagle-import:M2_SCREW_FOOT")
      (libsource (lib "eagle-import") (part "M2_SCREW_DEV"))
    )
    (comp (ref "U$16")
      (value "M2_SCREW_DEV")
      (footprint "eagle-import:M2_SCREW_FOOT")
      (libsource (lib "eagle-import") (part "M2_SCREW_DEV"))
    )
    (comp (ref "U$17")
      (value "M2_SCREW_DEV")
      (footprint "eagle-import:M2_SCREW_FOOT")
      (libsource (lib "eagle-import") (part "M2_SCREW_DEV"))
    )
    (comp (ref "U$19")
      (value "V_REG_TPS61040SMD")
      (footprint "eagle-import:SOT23-5")
      (libsource (lib "eagle-import") (part "V_REG_TPS61040SMD"))
    )
    (comp (ref "U$20")
      (value "M2_SCREW_DEV")
      (footprint "eagle-import:M2_SCREW_FOOT")
      (libsource (lib "eagle-import") (part "M2_SCREW_DEV"))
    )
    (comp (ref "U$21")
      (value "M2_SCREW_DEV")
      (footprint "eagle-import:M2_SCREW_FOOT")
      (libsource (lib "eagle-import") (part "M2_SCREW_DEV"))
    )
    (comp (ref "U$22")
      (value "M2_SCREW_DEV")
      (footprint "eagle-import:M2_SCREW_FOOT")
      (libsource (lib "eagle-import") (part "M2_SCREW_DEV"))
    )
    (comp (ref "U1")
      (value "USBC_16P")
      (footprint "eagle-import:USBC_16P_FOOT")
      (libsource (lib "eagle-import") (part "USBC_16P"))
    )
    (comp (ref "U2")
      (value "USBC_16P")
      (footprint "eagle-import:USBC_16P_FOOT")
      (libsource (lib "eagle-import") (part "USBC_16P"))
    )
    (comp (ref "U3")
      (value "ESP32-S3FN8")
      (footprint "eagle-import:QFN40P700X700X90-57N")
      (fields (field (name "MF") "Espressif Systems"))
      (libsource (lib "eagle-import") (part "ESP32-S3FN8"))
    )
    (comp (ref "X1")
      (value "ANTENNA_U.FL")
      (footprint "eagle-import:U.FL")
      (libsource (lib "eagle-import") (part "ANTENNA_U.FL"))
    )
    (comp (ref "Y1")
      (value "16MHz_12pF")
      (footprint "eagle-import:CRYSTAL-SMD-3.2X2.5MM")
      (libsource (lib "eagle-import") (part "CRYSTAL-26MHZSMD-3.2X2.5"))
    )
  )
  (nets
    (net (code "1") (name "+3V3") (class "Default")
      (node (ref "C11") (pin "2") (pinfunction "2_2") (pintype "passive"))
      (node (ref "C12") (pin "2") (pinfunction "2_2") (pintype "passive"))
      (node (ref "C13") (pin "2") (pinfunction "2_2") (pintype "passive"))
      (node (ref "C14") (pin "2") (pinfunction "2_2") (pintype "passive"))
      (node (ref "C15") (pin "2") (pinfunction "2_2") (pintype "passive"))
      (node (ref "C16") (pin "2") (pinfunction "2_2") (pintype "passive"))
      (node (ref "C17") (pin "2") (pinfunction "2_2") (pintype "passive"))
      (node (ref "C18") (pin "2") (pinfunction "2_2") (pintype "passive"))
      (node (ref "C19") (pin "2") (pinfunction "2_2") (pintype "passive"))
      (node (ref "C20") (pin "2") (pinfunction "2_2") (pintype "passive"))
      (node (ref "C21") (pin "2") (pinfunction "2_2") (pintype "passive"))
      (node (ref "C22") (pin "2") (pinfunction "2_2") (pintype "passive"))
      (node (ref "C23") (pin "2") (pinfunction "2_2") (pintype "passive"))
      (node (ref "C24") (pin "2") (pinfunction "2_2") (pintype "passive"))
      (node (ref "C25") (pin "2") (pinfunction "2_2") (pintype "passive"))
      (node (ref "C26") (pin "2") (pinfunction "2_2") (pintype "passive"))
      (node (ref "C27") (pin "1") (pinfunction "1_1") (pintype "passive"))
      (node (ref "C28") (pin "2") (pinfunction "2_2") (pintype "passive"))
      (node (ref "C30") (pin "2") (pinfunction "2_2") (pintype "passive"))
      (node (ref "C33") (pin "2") (pinfunction "2_2") (pintype "passive"))
      (node (ref "C36") (pin "2") (pinfunction "2_2") (pintype "passive"))
      (node (ref "C37") (pin "2") (pinfunction "2_2") (pintype "passive"))
      (node (ref "C38") (pin "2") (pinfunction "2_2") (pintype "passive"))
      (node (ref "C39") (pin "2") (pinfunction "2_2") (pintype "passive"))
      (node (ref "C41") (pin "2") (pinfunction "2_2") (pintype "passive"))
      (node (ref "C42") (pin "2") (pinfunction "2_2") (pintype "passive"))
      (node (ref "C43") (pin "2") (pinfunction "2_2") (pintype "passive"))
      (node (ref "C44") (pin "2") (pinfunction "2_2") (pintype "passive"))
      (node (ref "C45") (pin "2") (pinfunction "2_2") (pintype "passive"))
      (node (ref "C5") (pin "2") (pinfunction "2_2") (pintype "passive"))
      (node (ref "C6") (pin "2") (pinfunction "2_2") (pintype "passive"))
      (node (ref "C7") (pin "2") (pinfunction "2_2") (pintype "passive"))
      (node (ref "IC2") (pin "2") (pinfunction "VOUT_2") (pintype "output"))
      (node (ref "IC2") (pin "4") (pinfunction "VOUT_4") (pintype "output"))
      (node (ref "L2") (pin "1") (pinfunction "1_1") (pintype "passive"))
      (node (ref "LED_R1C1") (pin "VDD") (pinfunction "VDD_VDD") (pintype "power_in"))
      (node (ref "LED_R1C2") (pin "VDD") (pinfunction "VDD_VDD") (pintype "power_in"))
      (node (ref "LED_R1C3") (pin "VDD") (pinfunction "VDD_VDD") (pintype "power_in"))
      (node (ref "LED_R1C4") (pin "VDD") (pinfunction "VDD_VDD") (pintype "power_in"))
      (node (ref "LED_R2C1") (pin "VDD") (pinfunction "VDD_VDD") (pintype "power_in"))
      (node (ref "LED_R2C2") (pin "VDD") (pinfunction "VDD_VDD") (pintype "power_in"))
      (node (ref "LED_R2C3") (pin "VDD") (pinfunction "VDD_VDD") (pintype "power_in"))
      (node (ref "LED_R2C4") (pin "VDD") (pinfunction "VDD_VDD") (pintype "power_in"))
      (node (ref "LED_R3C1") (pin "VDD") (pinfunction "VDD_VDD") (pintype "power_in"))
      (node (ref "LED_R3C2") (pin "VDD") (pinfunction "VDD_VDD") (pintype "power_in"))
      (node (ref "LED_R3C3") (pin "VDD") (pinfunction "VDD_VDD") (pintype "power_in"))
      (node (ref "LED_R3C4") (pin "VDD") (pinfunction "VDD_VDD") (pintype "power_in"))
      (node (ref "LED_R4C1") (pin "VDD") (pinfunction "VDD_VDD") (pintype "power_in"))
      (node (ref "LED_R4C2") (pin "VDD") (pinfunction "VDD_VDD") (pintype "power_in"))
      (node (ref "LED_R4C3") (pin "VDD") (pinfunction "VDD_VDD") (pintype "power_in"))
      (node (ref "LED_R4C4") (pin "VDD") (pinfunction "VDD_VDD") (pintype "power_in"))
      (node (ref "LED_R5C1") (pin "VDD") (pinfunction "VDD_VDD") (pintype "power_in"))
      (node (ref "LED_R5C2") (pin "VDD") (pinfunction "VDD_VDD") (pintype "power_in"))
      (node (ref "LED_R5C3") (pin "VDD") (pinfunction "VDD_VDD") (pintype "power_in"))
      (node (ref "LED_R5C4") (pin "VDD") (pinfunction "VDD_VDD") (pintype "power_in"))
      (node (ref "R11") (pin "1") (pinfunction "1_1") (pintype "passive"))
      (node (ref "R12") (pin "2") (pinfunction "2_2") (pintype "passive"))
      (node (ref "R16") (pin "2") (pinfunction "2_2") (pintype "passive"))
      (node (ref "R2") (pin "1") (pinfunction "1_1") (pintype "passive"))
      (node (ref "SD1") (pin "4") (pinfunction "VDD_4") (pintype "power_in"))
      (node (ref "U$19") (pin "4") (pinfunction "EN_4") (pintype "bidirectional"))
      (node (ref "U$19") (pin "5") (pinfunction "VIN_5") (pintype "bidirectional"))
      (node (ref "U$2") (pin "4") (pinfunction "VDD_4") (pintype "bidirectional"))
      (node (ref "U$3") (pin "1") (pinfunction "1_1") (pintype "passive"))
      (node (ref "U$3") (pin "2") (pinfunction "2_2") (pintype "passive"))
      (node (ref "U3") (pin "2") (pinfunction "VDD3P3_2") (pintype "power_in"))
      (node (ref "U3") (pin "20") (pinfunction "VDD3P3_RTC_20") (pintype "power_in"))
      (node (ref "U3") (pin "3") (pinfunction "VDD3P3_3") (pintype "power_in"))
      (node (ref "U3") (pin "46") (pinfunction "VDD3P3_CPU_46") (pintype "power_in"))
      (node (ref "U3") (pin "55") (pinfunction "VDDA1_55") (pintype "power_in"))
      (node (ref "U3") (pin "56") (pinfunction "VDDA2_56") (pintype "power_in"))
    )
    (net (code "2") (name "/CARD_DET") (class "Default")
      (node (ref "SD1") (pin "9") (pinfunction "~{CARD}_9") (pintype "passive"))
      (node (ref "U3") (pin "12") (pinfunction "GPIO7_12") (pintype "bidirectional"))
    )
    (net (code "3") (name "/MISO") (class "Default")
      (node (ref "SD1") (pin "7") (pinfunction "DAT0(DO)_7") (pintype "bidirectional"))
      (node (ref "U3") (pin "13") (pinfunction "GPIO8_13") (pintype "bidirectional"))
    )
    (net (code "4") (name "/MOSI") (class "Default")
      (node (ref "JP5") (pin "5") (pinfunction "5_5") (pintype "passive"))
      (node (ref "SD1") (pin "3") (pinfunction "CMD(DI)_3") (pintype "bidirectional"))
      (node (ref "U$2") (pin "10") (pinfunction "D1_10") (pintype "bidirectional"))
      (node (ref "U3") (pin "15") (pinfunction "GPIO10_15") (pintype "bidirectional"))
    )
    (net (code "5") (name "/N$43") (class "Default")
      (node (ref "R11") (pin "2") (pinfunction "2_2") (pintype "passive"))
      (node (ref "SD1") (pin "2") (pinfunction "CD/DAT3(~{CS})_2") (pintype "bidirectional"))
    )
    (net (code "6") (name "/SCLK") (class "Default")
      (node (ref "JP5") (pin "4") (pinfunction "4_4") (pintype "passive"))
      (node (ref "SD1") (pin "5") (pinfunction "CLK(SCLK)_5") (pintype "input"))
      (node (ref "U$2") (pin "9") (pinfunction "D0_9") (pintype "bidirectional"))
      (node (ref "U3") (pin "14") (pinfunction "GPIO9_14") (pintype "bidirectional"))
    )
    (net (code "7") (name "/SW_R1C1") (class "Default")
      (node (ref "SWR1C1") (pin "2") (pinfunction "1_2") (pintype "passive"))
      (node (ref "U3") (pin "48") (pinfunction "MTMS_48") (pintype "bidirectional"))
    )
    (net (code "8") (name "/SW_R1C2") (class "Default")
      (node (ref "JP3") (pin "1") (pinfunction "1_1") (pintype "passive"))
      (node (ref "R18") (pin "1") (pinfunction "1_1") (pintype "passive"))
      (node (ref "SWR1C2") (pin "2") (pinfunction "1_2") (pintype "passive"))
    )
    (net (code "9") (name "/SW_R1C3") (class "Default")
      (node (ref "SWR1C3") (pin "2") (pinfunction "1_2") (pintype "passive"))
      (node (ref "U3") (pin "50") (pinfunction "U0RXD_50") (pintype "bidirectional"))
    )
    (net (code "10") (name "/SW_R1C4") (class "Default")
      (node (ref "SWR1C4") (pin "2") (pinfunction "1_2") (pintype "passive"))
      (node (ref "U3") (pin "51") (pinfunction "GPIO45_51") (pintype "bidirectional"))
    )
    (net (code "11") (name "/SW_R2C1") (class "Default")
      (node (ref "SWR2C1") (pin "2") (pinfunction "1_2") (pintype "passive"))
      (node (ref "U3") (pin "43") (pinfunction "GPIO38_43") (pintype "bidirectional"))
    )
    (net (code "12") (name "/SW_R2C2") (class "Default")
      (node (ref "SWR2C2") (pin "2") (pinfunction "1_2") (pintype "passive"))
      (node (ref "U3") (pin "44") (pinfunction "MTCK_44") (pintype "bidirectional"))
    )
    (net (code "13") (name "/SW_R2C3") (class "Default")
      (node (ref "SWR2C3") (pin "2") (pinfunction "1_2") (pintype "passive"))
      (node (ref "U3") (pin "45") (pinfunction "MTDO_45") (pintype "bidirectional"))
    )
    (net (code "14") (name "/SW_R2C4") (class "Default")
      (node (ref "SWR2C4") (pin "2") (pinfunction "1_2") (pintype "passive"))
      (node (ref "U3") (pin "47") (pinfunction "MTDI_47") (pintype "bidirectional"))
    )
    (net (code "15") (name "/SW_R3C1") (class "Default")
      (node (ref "SWR3C1") (pin "2") (pinfunction "1_2") (pintype "passive"))
      (node (ref "U3") (pin "42") (pinfunction "GPIO37_42") (pintype "bidirectional"))
    )
    (net (code "16") (name "/SW_R3C2") (class "Default")
      (node (ref "SWR3C2") (pin "2") (pinfunction "1_2") (pintype "passive"))
      (node (ref "U3") (pin "41") (pinfunction "GPIO36_41") (pintype "bidirectional"))
    )
    (net (code "17") (name "/SW_R3C3") (class "Default")
      (node (ref "SWR3C3") (pin "2") (pinfunction "1_2") (pintype "passive"))
      (node (ref "U3") (pin "40") (pinfunction "GPIO35_40") (pintype "bidirectional"))
    )
    (net (code "18") (name "/SW_R3C4") (class "Default")
      (node (ref "SWR3C4") (pin "2") (pinfunction "1_2") (pintype "passive"))
      (node (ref "U3") (pin "39") (pinfunction "GPIO34_39") (pintype "bidirectional"))
    )
    (net (code "19") (name "/SW_R4C1") (class "Default")
      (node (ref "SWR4C1") (pin "2") (pinfunction "1_2") (pintype "passive"))
      (node (ref "U3") (pin "27") (pinfunction "GPIO21_27") (pintype "bidirectional"))
    )
    (net (code "20") (name "/SW_R4C2") (class "Default")
      (node (ref "SWR4C2") (pin "2") (pinfunction "1_2") (pintype "passive"))
      (node (ref "U3") (pin "36") (pinfunction "SPICLK_N_36") (pintype "bidirectional"))
    )
    (net (code "21") (name "/SW_R4C3") (class "Default")
      (node (ref "SWR4C3") (pin "2") (pinfunction "1_2") (pintype "passive"))
      (node (ref "U3") (pin "37") (pinfunction "SPICLK_P_37") (pintype "bidirectional"))
    )
    (net (code "22") (name "/SW_R4C4") (class "Default")
      (node (ref "SWR4C4") (pin "2") (pinfunction "1_2") (pintype "passive"))
      (node (ref "U3") (pin "38") (pinfunction "GPIO33_38") (pintype "bidirectional"))
    )
    (net (code "23") (name "/SW_R5C1") (class "Default")
      (node (ref "SWR5C1") (pin "2") (pinfunction "1_2") (pintype "passive"))
      (node (ref "U3") (pin "21") (pinfunction "XTAL_32K_P_21") (pintype "bidirectional"))
    )
    (net (code "24") (name "/SW_R5C2") (class "Default")
      (node (ref "SWR5C2") (pin "2") (pinfunction "1_2") (pintype "passive"))
      (node (ref "U3") (pin "22") (pinfunction "XTAL_32K_N_22") (pintype "bidirectional"))
    )
    (net (code "25") (name "/SW_R5C3") (class "Default")
      (node (ref "SWR5C3") (pin "2") (pinfunction "1_2") (pintype "passive"))
      (node (ref "U3") (pin "23") (pinfunction "GPIO17_23") (pintype "bidirectional"))
    )
    (net (code "26") (name "/SW_R5C4") (class "Default")
      (node (ref "SWR5C4") (pin "2") (pinfunction "1_2") (pintype "passive"))
      (node (ref "U3") (pin "24") (pinfunction "GPIO18_24") (pintype "bidirectional"))
    )
    (net (code "27") (name "/USB_DN") (class "Default")
      (node (ref "U1") (pin "A7") (pinfunction "DN1_A7") (pintype "bidirectional"))
      (node (ref "U1") (pin "B7") (pinfunction "DN2_B7") (pintype "bidirectional"))
      (node (ref "U2") (pin "A7") (pinfunction "DN1_A7") (pintype "bidirectional"))
      (node (ref "U2") (pin "B7") (pinfunction "DN2_B7") (pintype "bidirectional"))
      (node (ref "U3") (pin "25") (pinfunction "GPIO19_25") (pintype "bidirectional"))
    )
    (net (code "28") (name "/USB_DP") (class "Default")
      (node (ref "U1") (pin "A6") (pinfunction "DP1_A6") (pintype "bidirectional"))
      (node (ref "U1") (pin "B6") (pinfunction "DP2_B6") (pintype "bidirectional"))
      (node (ref "U2") (pin "A6") (pinfunction "DP1_A6") (pintype "bidirectional"))
      (node (ref "U2") (pin "B6") (pinfunction "DP2_B6") (pintype "bidirectional"))
      (node (ref "U3") (pin "26") (pinfunction "GPIO20_26") (pintype "bidirectional"))
    )
    (net (code "29") (name "/VDD_SPI") (class "Default")
      (node (ref "U3") (pin "29") (pinfunction "VDD_SPI_29") (pintype "power_in"))
    )
    (net (code "30") (name "12V") (class "Default")
      (node (ref "C31") (pin "2") (pinfunction "2_2") (pintype "passive"))
      (node (ref "C32") (pin "2") (pinfunction "2_2") (pintype "passive"))
      (node (ref "C35") (pin "2") (pinfunction "2_2") (pintype "passive"))
      (node (ref "C40") (pin "2") (pinfunction "2_2") (pintype "passive"))
      (node (ref "C46") (pin "2") (pinfunction "2_2") (pintype "passive"))
      (node (ref "D1") (pin "C") (pinfunction "C_C") (pintype "passive"))
      (node (ref "R7") (pin "1") (pinfunction "1_1") (pintype "passive"))
      (node (ref "U$2") (pin "11") (pinfunction "VCC2_11") (pintype "bidirectional"))
      (node (ref "U$2") (pin "2") (pinfunction "VCC_2") (pintype "bidirectional"))
    )
    (net (code "31") (name "GND") (class "Default")
      (node (ref "C1") (pin "1") (pinfunction "1_1") (pintype "passive"))
      (node (ref "C10") (pin "1") (pinfunction "1_1") (pintype "passive"))
      (node (ref "C11") (pin "1") (pinfunction "1_1") (pintype "passive"))
      (node (ref "C12") (pin "1") (pinfunction "1_1") (pintype "passive"))
      (node (ref "C13") (pin "1") (pinfunction "1_1") (pintype "passive"))
      (node (ref "C14") (pin "1") (pinfunction "1_1") (pintype "passive"))
      (node (ref "C15") (pin "1") (pinfunction "1_1") (pintype "passive"))
      (node (ref "C16") (pin "1") (pinfunction "1_1") (pintype "passive"))
      (node (ref "C17") (pin "1") (pinfunction "1_1") (pintype "passive"))
      (node (ref "C18") (pin "1") (pinfunction "1_1") (pintype "passive"))
      (node (ref "C19") (pin "1") (pinfunction "1_1") (pintype "passive"))
      (node (ref "C2") (pin "1") (pinfunction "1_1") (pintype "passive"))
      (node (ref "C20") (pin "1") (pinfunction "1_1") (pintype "passive"))
      (node (ref "C21") (pin "1") (pinfunction "1_1") (pintype "passive"))
      (node (ref "C22") (pin "1") (pinfunction "1_1") (pintype "passive"))
      (node (ref "C23") (pin "1") (pinfunction "1_1") (pintype "passive"))
      (node (ref "C24") (pin "1") (pinfunction "1_1") (pintype "passive"))
      (node (ref "C25") (pin "1") (pinfunction "1_1") (pintype "passive"))
      (node (ref "C26") (pin "1") (pinfunction "1_1") (pintype "passive"))
      (node (ref "C27") (pin "2") (pinfunction "2_2") (pintype "passive"))
      (node (ref "C28") (pin "1") (pinfunction "1_1") (pintype "passive"))
      (node (ref "C29") (pin "1") (pinfunction "1_1") (pintype "passive"))
      (node (ref "C3") (pin "2") (pinfunction "2_2") (pintype "passive"))
      (node (ref "C30") (pin "1") (pinfunction "1_1") (pintype "passive"))
      (node (ref "C31") (pin "1") (pinfunction "1_1") (pintype "passive"))
      (node (ref "C32") (pin "1") (pinfunction "1_1") (pintype "passive"))
      (node (ref "C33") (pin "1") (pinfunction "1_1") (pintype "passive"))
      (node (ref "C34") (pin "1") (pinfunction "1_1") (pintype "passive"))
      (node (ref "C36") (pin "1") (pinfunction "1_1") (pintype "passive"))
      (node (ref "C37") (pin "1") (pinfunction "1_1") (pintype "passive"))
      (node (ref "C38") (pin "1") (pinfunction "1_1") (pintype "passive"))
      (node (ref "C39") (pin "1") (pinfunction "1_1") (pintype "passive"))
      (node (ref "C4") (pin "2") (pinfunction "2_2") (pintype "passive"))
      (node (ref "C40") (pin "1") (pinfunction "1_1") (pintype "passive"))
      (node (ref "C41") (pin "1") (pinfunction "1_1") (pintype "passive"))
      (node (ref "C42") (pin "1") (pinfunction "1_1") (pintype "passive"))
      (node (ref "C43") (pin "1") (pinfunction "1_1") (pintype "passive"))
      (node (ref "C44") (pin "1") (pinfunction "1_1") (pintype "passive"))
      (node (ref "C45") (pin "1") (pinfunction "1_1") (pintype "passive"))
      (node (ref "C46") (pin "1") (pinfunction "1_1") (pintype "passive"))
      (node (ref "C5") (pin "1") (pinfunction "1_1") (pintype "passive"))
      (node (ref "C6") (pin "1") (pinfunction "1_1") (pintype "passive"))
      (node (ref "C7") (pin "1") (pinfunction "1_1") (pintype "passive"))
      (node (ref "C8") (pin "2") (pinfunction "2_2") (pintype "passive"))
      (node (ref "C9") (pin "1") (pinfunction "1_1") (pintype "passive"))
      (node (ref "IC2") (pin "1") (pinfunction "GND_1") (pintype "power_in"))
      (node (ref "JP5") (pin "6") (pinfunction "6_6") (pintype "passive"))
      (node (ref "LED_R1C1") (pin "GND") (pinfunction "GND_GND") (pintype "power_in"))
      (node (ref "LED_R1C2") (pin "GND") (pinfunction "GND_GND") (pintype "power_in"))
      (node (ref "LED_R1C3") (pin "GND") (pinfunction "GND_GND") (pintype "power_in"))
      (node (ref "LED_R1C4") (pin "GND") (pinfunction "GND_GND") (pintype "power_in"))
      (node (ref "LED_R2C1") (pin "GND") (pinfunction "GND_GND") (pintype "power_in"))
      (node (ref "LED_R2C2") (pin "GND") (pinfunction "GND_GND") (pintype "power_in"))
      (node (ref "LED_R2C3") (pin "GND") (pinfunction "GND_GND") (pintype "power_in"))
      (node (ref "LED_R2C4") (pin "GND") (pinfunction "GND_GND") (pintype "power_in"))
      (node (ref "LED_R3C1") (pin "GND") (pinfunction "GND_GND") (pintype "power_in"))
      (node (ref "LED_R3C2") (pin "GND") (pinfunction "GND_GND") (pintype "power_in"))
      (node (ref "LED_R3C3") (pin "GND") (pinfunction "GND_GND") (pintype "power_in"))
      (node (ref "LED_R3C4") (pin "GND") (pinfunction "GND_GND") (pintype "power_in"))
      (node (ref "LED_R4C1") (pin "GND") (pinfunction "GND_GND") (pintype "power_in"))
      (node (ref "LED_R4C2") (pin "GND") (pinfunction "GND_GND") (pintype "power_in"))
      (node (ref "LED_R4C3") (pin "GND") (pinfunction "GND_GND") (pintype "power_in"))
      (node (ref "LED_R4C4") (pin "GND") (pinfunction "GND_GND") (pintype "power_in"))
      (node (ref "LED_R5C1") (pin "GND") (pinfunction "GND_GND") (pintype "power_in"))
      (node (ref "LED_R5C2") (pin "GND") (pinfunction "GND_GND") (pintype "power_in"))
      (node (ref "LED_R5C3") (pin "GND") (pinfunction "GND_GND") (pintype "power_in"))
      (node (ref "LED_R5C4") (pin "GND") (pinfunction "GND_GND") (pintype "power_in"))
      (node (ref "R1") (pin "2") (pinfunction "2_2") (pintype "passive"))
      (node (ref "R10") (pin "2") (pinfunction "2_2") (pintype "passive"))
      (node (ref "R17") (pin "1") (pinfunction "1_1") (pintype "passive"))
      (node (ref "R3") (pin "2") (pinfunction "2_2") (pintype "passive"))
      (node (ref "R4") (pin "2") (pinfunction "2_2") (pintype "passive"))
      (node (ref "R5") (pin "1") (pinfunction "1_1") (pintype "passive"))
      (node (ref "R6") (pin "1") (pinfunction "1_1") (pintype "passive"))
      (node (ref "R9") (pin "2") (pinfunction "2_2") (pintype "passive"))
      (node (ref "SD1") (pin "6") (pinfunction "VSS_6") (pintype "power_in"))
      (node (ref "SD1") (pin "S1") (pinfunction "S1_S1") (pintype "passive"))
      (node (ref "SD1") (pin "S2") (pinfunction "S2_S2") (pintype "passive"))
      (node (ref "SD1") (pin "S3") (pinfunction "S3_S3") (pintype "passive"))
      (node (ref "SD1") (pin "S4") (pinfunction "S4_S4") (pintype "passive"))
      (node (ref "SW1") (pin "A") (pinfunction "P_A") (pintype "passive"))
      (node (ref "SW1") (pin "A'") (pinfunction "P1_A'") (pintype "passive"))
      (node (ref "SW2") (pin "A") (pinfunction "P_A") (pintype "passive"))
      (node (ref "SW2") (pin "A'") (pinfunction "P1_A'") (pintype "passive"))
      (node (ref "SW21") (pin "C") (pinfunction "C_C") (pintype "passive"))
      (node (ref "SW21") (pin "E") (pinfunction "2_E") (pintype "passive"))
      (node (ref "SW22") (pin "C") (pinfunction "C_C") (pintype "passive"))
      (node (ref "SW22") (pin "E") (pinfunction "2_E") (pintype "passive"))
      (node (ref "SW3") (pin "P$1") (pinfunction "1_P$1") (pintype "bidirectional"))
      (node (ref "SW3") (pin "P$4") (pinfunction "4_P$4") (pintype "bidirectional"))
      (node (ref "SWR1C1") (pin "1") (pinfunction "2_1") (pintype "passive"))
      (node (ref "SWR1C2") (pin "1") (pinfunction "2_1") (pintype "passive"))
      (node (ref "SWR1C3") (pin "1") (pinfunction "2_1") (pintype "passive"))
      (node (ref "SWR1C4") (pin "1") (pinfunction "2_1") (pintype "passive"))
      (node (ref "SWR2C1") (pin "1") (pinfunction "2_1") (pintype "passive"))
      (node (ref "SWR2C2") (pin "1") (pinfunction "2_1") (pintype "passive"))
      (node (ref "SWR2C3") (pin "1") (pinfunction "2_1") (pintype "passive"))
      (node (ref "SWR2C4") (pin "1") (pinfunction "2_1") (pintype "passive"))
      (node (ref "SWR3C1") (pin "1") (pinfunction "2_1") (pintype "passive"))
      (node (ref "SWR3C2") (pin "1") (pinfunction "2_1") (pintype "passive"))
      (node (ref "SWR3C3") (pin "1") (pinfunction "2_1") (pintype "passive"))
      (node (ref "SWR3C4") (pin "1") (pinfunction "2_1") (pintype "passive"))
      (node (ref "SWR4C1") (pin "1") (pinfunction "2_1") (pintype "passive"))
      (node (ref "SWR4C2") (pin "1") (pinfunction "2_1") (pintype "passive"))
      (node (ref "SWR4C3") (pin "1") (pinfunction "2_1") (pintype "passive"))
      (node (ref "SWR4C4") (pin "1") (pinfunction "2_1") (pintype "passive"))
      (node (ref "SWR5C1") (pin "1") (pinfunction "2_1") (pintype "passive"))
      (node (ref "SWR5C2") (pin "1") (pinfunction "2_1") (pintype "passive"))
      (node (ref "SWR5C3") (pin "1") (pinfunction "2_1") (pintype "passive"))
      (node (ref "SWR5C4") (pin "1") (pinfunction "2_1") (pintype "passive"))
      (node (ref "U$19") (pin "2") (pinfunction "GND_2") (pintype "bidirectional"))
      (node (ref "U$2") (pin "1") (pinfunction "GND_1") (pintype "bidirectional"))
      (node (ref "U$2") (pin "12") (pinfunction "GND2_12") (pintype "bidirectional"))
      (node (ref "U$2") (pin "31") (pinfunction "SHIELD_31") (pintype "bidirectional"))
      (node (ref "U$2") (pin "32") (pinfunction "SHIELD_32") (pintype "bidirectional"))
      (node (ref "U1") (pin "A1B12") (pinfunction "GND_A1B12") (pintype "bidirectional"))
      (node (ref "U1") (pin "B11A12") (pinfunction "GND_B11A12") (pintype "bidirectional"))
      (node (ref "U1") (pin "P$13") (pinfunction "GND_P$13") (pintype "bidirectional"))
      (node (ref "U1") (pin "P$14") (pinfunction "GND_P$14") (pintype "bidirectional"))
      (node (ref "U1") (pin "P$15") (pinfunction "GND_P$15") (pintype "bidirectional"))
      (node (ref "U1") (pin "P$16") (pinfunction "GND_P$16") (pintype "bidirectional"))
      (node (ref "U2") (pin "A1B12") (pinfunction "GND_A1B12") (pintype "bidirectional"))
      (node (ref "U2") (pin "B11A12") (pinfunction "GND_B11A12") (pintype "bidirectional"))
      (node (ref "U2") (pin "P$13") (pinfunction "GND_P$13") (pintype "bidirectional"))
      (node (ref "U2") (pin "P$14") (pinfunction "GND_P$14") (pintype "bidirectional"))
      (node (ref "U2") (pin "P$15") (pinfunction "GND_P$15") (pintype "bidirectional"))
      (node (ref "U2") (pin "P$16") (pinfunction "GND_P$16") (pintype "bidirectional"))
      (node (ref "U3") (pin "57") (pinfunction "GND_57") (pintype "power_in"))
      (node (ref "X1") (pin "1") (pinfunction "GND_1") (pintype "passive"))
      (node (ref "X1") (pin "2") (pinfunction "GND_2") (pintype "passive"))
      (node (ref "Y1") (pin "2") (pinfunction "3_2") (pintype "passive"))
      (node (ref "Y1") (pin "4") (pinfunction "3_4") (pintype "passive"))
    )
    (net (code "32") (name "Net-(IC2-VIN)") (class "Default")
      (node (ref "C29") (pin "2") (pinfunction "2_2") (pintype "passive"))
      (node (ref "IC2") (pin "3") (pinfunction "VIN_3") (pintype "input"))
      (node (ref "JP2") (pin "2") (pinfunction "2_2") (pintype "passive"))
    )
    (net (code "33") (name "Net-(JP2-Pad1)") (class "Default")
      (node (ref "JP2") (pin "1") (pinfunction "1_1") (pintype "passive"))
      (node (ref "U1") (pin "A4B9") (pinfunction "VBUS_A4B9") (pintype "bidirectional"))
      (node (ref "U1") (pin "B4A9") (pinfunction "VBUS_B4A9") (pintype "bidirectional"))
      (node (ref "U2") (pin "A4B9") (pinfunction "VBUS_A4B9") (pintype "bidirectional"))
      (node (ref "U2") (pin "B4A9") (pinfunction "VBUS_B4A9") (pintype "bidirectional"))
    )
    (net (code "34") (name "Net-(LED_R1C1-DI)") (class "Default")
      (node (ref "LED_R1C1") (pin "DIN") (pinfunction "DI_DIN") (pintype "input"))
      (node (ref "LED_R1C2") (pin "DOUT") (pinfunction "DO_DOUT") (pintype "output"))
    )
    (net (code "35") (name "Net-(LED_R1C1-DO)") (class "Default")
      (node (ref "LED_R1C1") (pin "DOUT") (pinfunction "DO_DOUT") (pintype "output"))
      (node (ref "LED_R2C1") (pin "DIN") (pinfunction "DI_DIN") (pintype "input"))
    )
    (net (code "36") (name "Net-(LED_R1C2-DI)") (class "Default")
      (node (ref "LED_R1C2") (pin "DIN") (pinfunction "DI_DIN") (pintype "input"))
      (node (ref "LED_R1C3") (pin "DOUT") (pinfunction "DO_DOUT") (pintype "output"))
    )
    (net (code "37") (name "Net-(LED_R1C3-DI)") (class "Default")
      (node (ref "LED_R1C3") (pin "DIN") (pinfunction "DI_DIN") (pintype "input"))
      (node (ref "LED_R1C4") (pin "DOUT") (pinfunction "DO_DOUT") (pintype "output"))
    )
    (net (code "38") (name "Net-(LED_R1C4-DI)") (class "Default")
      (node (ref "LED_R1C4") (pin "DIN") (pinfunction "DI_DIN") (pintype "input"))
      (node (ref "R5") (pin "2") (pinfunction "2_2") (pintype "passive"))
      (node (ref "U3") (pin "52") (pinfunction "GPIO46_52") (pintype "bidirectional"))
    )
    (net (code "39") (name "Net-(LED_R2C1-DO)") (class "Default")
      (node (ref "LED_R2C1") (pin "DOUT") (pinfunction "DO_DOUT") (pintype "output"))
      (node (ref "LED_R2C2") (pin "DIN") (pinfunction "DI_DIN") (pintype "input"))
    )
    (net (code "40") (name "Net-(LED_R2C2-DO)") (class "Default")
      (node (ref "LED_R2C2") (pin "DOUT") (pinfunction "DO_DOUT") (pintype "output"))
      (node (ref "LED_R2C3") (pin "DIN") (pinfunction "DI_DIN") (pintype "input"))
    )
    (net (code "41") (name "Net-(LED_R2C3-DO)") (class "Default")
      (node (ref "LED_R2C3") (pin "DOUT") (pinfunction "DO_DOUT") (pintype "output"))
      (node (ref "LED_R2C4") (pin "DIN") (pinfunction "DI_DIN") (pintype "input"))
    )
    (net (code "42") (name "Net-(LED_R2C4-DO)") (class "Default")
      (node (ref "LED_R2C4") (pin "DOUT") (pinfunction "DO_DOUT") (pintype "output"))
      (node (ref "LED_R3C4") (pin "DIN") (pinfunction "DI_DIN") (pintype "input"))
    )
    (net (code "43") (name "Net-(LED_R3C1-DI)") (class "Default")
      (node (ref "LED_R3C1") (pin "DIN") (pinfunction "DI_DIN") (pintype "input"))
      (node (ref "LED_R3C2") (pin "DOUT") (pinfunction "DO_DOUT") (pintype "output"))
    )
    (net (code "44") (name "Net-(LED_R3C1-DO)") (class "Default")
      (node (ref "LED_R3C1") (pin "DOUT") (pinfunction "DO_DOUT") (pintype "output"))
      (node (ref "LED_R4C1") (pin "DIN") (pinfunction "DI_DIN") (pintype "input"))
    )
    (net (code "45") (name "Net-(LED_R3C2-DI)") (class "Default")
      (node (ref "LED_R3C2") (pin "DIN") (pinfunction "DI_DIN") (pintype "input"))
      (node (ref "LED_R3C3") (pin "DOUT") (pinfunction "DO_DOUT") (pintype "output"))
    )
    (net (code "46") (name "Net-(LED_R3C3-DI)") (class "Default")
      (node (ref "LED_R3C3") (pin "DIN") (pinfunction "DI_DIN") (pintype "input"))
      (node (ref "LED_R3C4") (pin "DOUT") (pinfunction "DO_DOUT") (pintype "output"))
    )
    (net (code "47") (name "Net-(LED_R4C1-DO)") (class "Default")
      (node (ref "LED_R4C1") (pin "DOUT") (pinfunction "DO_DOUT") (pintype "output"))
      (node (ref "LED_R4C2") (pin "DIN") (pinfunction "DI_DIN") (pintype "input"))
    )
    (net (code "48") (name "Net-(LED_R4C2-DO)") (class "Default")
      (node (ref "LED_R4C2") (pin "DOUT") (pinfunction "DO_DOUT") (pintype "output"))
      (node (ref "LED_R4C3") (pin "DIN") (pinfunction "DI_DIN") (pintype "input"))
    )
    (net (code "49") (name "Net-(LED_R4C3-DO)") (class "Default")
      (node (ref "LED_R4C3") (pin "DOUT") (pinfunction "DO_DOUT") (pintype "output"))
      (node (ref "LED_R4C4") (pin "DIN") (pinfunction "DI_DIN") (pintype "input"))
    )
    (net (code "50") (name "Net-(LED_R4C4-DO)") (class "Default")
      (node (ref "LED_R4C4") (pin "DOUT") (pinfunction "DO_DOUT") (pintype "output"))
      (node (ref "LED_R5C4") (pin "DIN") (pinfunction "DI_DIN") (pintype "input"))
    )
    (net (code "51") (name "Net-(LED_R5C1-DI)") (class "Default")
      (node (ref "LED_R5C1") (pin "DIN") (pinfunction "DI_DIN") (pintype "input"))
      (node (ref "LED_R5C2") (pin "DOUT") (pinfunction "DO_DOUT") (pintype "output"))
    )
    (net (code "52") (name "Net-(LED_R5C2-DI)") (class "Default")
      (node (ref "LED_R5C2") (pin "DIN") (pinfunction "DI_DIN") (pintype "input"))
      (node (ref "LED_R5C3") (pin "DOUT") (pinfunction "DO_DOUT") (pintype "output"))
    )
    (net (code "53") (name "Net-(LED_R5C3-DI)") (class "Default")
      (node (ref "LED_R5C3") (pin "DIN") (pinfunction "DI_DIN") (pintype "input"))
      (node (ref "LED_R5C4") (pin "DOUT") (pinfunction "DO_DOUT") (pintype "output"))
    )
    (net (code "54") (name "Net-(R8-Pad2)") (class "Default")
      (node (ref "R8") (pin "2") (pinfunction "2_2") (pintype "passive"))
      (node (ref "SW22") (pin "A") (pinfunction "A_A") (pintype "passive"))
    )
    (net (code "55") (name "Net-(R13-Pad2)") (class "Default")
      (node (ref "R13") (pin "2") (pinfunction "2_2") (pintype "passive"))
      (node (ref "SW22") (pin "B") (pinfunction "B_B") (pintype "passive"))
    )
    (net (code "56") (name "Net-(R14-Pad2)") (class "Default")
      (node (ref "R14") (pin "2") (pinfunction "2_2") (pintype "passive"))
      (node (ref "SW21") (pin "A") (pinfunction "A_A") (pintype "passive"))
    )
    (net (code "57") (name "Net-(R15-Pad2)") (class "Default")
      (node (ref "R15") (pin "2") (pinfunction "2_2") (pintype "passive"))
      (node (ref "SW21") (pin "B") (pinfunction "B_B") (pintype "passive"))
    )
    (net (code "58") (name "Net-(SW1-S)") (class "Default")
      (node (ref "SW1") (pin "B") (pinfunction "S_B") (pintype "passive"))
      (node (ref "SW1") (pin "B'") (pinfunction "S1_B'") (pintype "passive"))
      (node (ref "U3") (pin "18") (pinfunction "GPIO13_18") (pintype "bidirectional"))
    )
    (net (code "59") (name "Net-(SW2-S)") (class "Default")
      (node (ref "SW2") (pin "B") (pinfunction "S_B") (pintype "passive"))
      (node (ref "SW2") (pin "B'") (pinfunction "S1_B'") (pintype "passive"))
      (node (ref "U3") (pin "19") (pinfunction "GPIO14_19") (pintype "bidirectional"))
    )
    (net (code "60") (name "Net-(SW3-2)") (class "Default")
      (node (ref "C4") (pin "1") (pinfunction "1_1") (pintype "passive"))
      (node (ref "R2") (pin "2") (pinfunction "2_2") (pintype "passive"))
      (node (ref "SW3") (pin "P$2") (pinfunction "2_P$2") (pintype "bidirectional"))
      (node (ref "SW3") (pin "P$3") (pinfunction "3_P$3") (pintype "bidirectional"))
      (node (ref "U3") (pin "4") (pinfunction "CHIP_PU_4") (pintype "input"))
    )
    (net (code "61") (name "Net-(SW21B-1)") (class "Default")
      (node (ref "R16") (pin "1") (pinfunction "1_1") (pintype "passive"))
      (node (ref "SW21") (pin "D") (pinfunction "1_D") (pintype "passive"))
      (node (ref "U3") (pin "8") (pinfunction "GPIO3_8") (pintype "bidirectional"))
    )
    (net (code "62") (name "Net-(SW22B-1)") (class "Default")
      (node (ref "SW22") (pin "D") (pinfunction "1_D") (pintype "passive"))
      (node (ref "U3") (pin "5") (pinfunction "GPIO0_5") (pintype "bidirectional"))
    )
    (net (code "63") (name "Net-(U$2-CS)") (class "Default")
      (node (ref "JP5") (pin "1") (pinfunction "1_1") (pintype "passive"))
      (node (ref "R12") (pin "1") (pinfunction "1_1") (pintype "passive"))
      (node (ref "U$2") (pin "6") (pinfunction "CS_6") (pintype "bidirectional"))
      (node (ref "U3") (pin "17") (pinfunction "GPIO12_17") (pintype "bidirectional"))
    )
    (net (code "64") (name "Net-(U$2-DC)") (class "Default")
      (node (ref "JP5") (pin "3") (pinfunction "3_3") (pintype "passive"))
      (node (ref "U$2") (pin "8") (pinfunction "DC_8") (pintype "bidirectional"))
      (node (ref "U3") (pin "16") (pinfunction "GPIO11_16") (pintype "bidirectional"))
    )
    (net (code "65") (name "Net-(U$2-IREF)") (class "Default")
      (node (ref "R6") (pin "2") (pinfunction "2_2") (pintype "passive"))
      (node (ref "U$2") (pin "5") (pinfunction "IREF_5") (pintype "bidirectional"))
    )
    (net (code "66") (name "Net-(U$2-RES)") (class "Default")
      (node (ref "JP5") (pin "2") (pinfunction "2_2") (pintype "passive"))
      (node (ref "R17") (pin "2") (pinfunction "2_2") (pintype "passive"))
      (node (ref "U$2") (pin "7") (pinfunction "RES_7") (pintype "bidirectional"))
      (node (ref "U3") (pin "11") (pinfunction "GPIO6_11") (pintype "bidirectional"))
    )
    (net (code "67") (name "Net-(U$2-VCOMH)") (class "Default")
      (node (ref "C34") (pin "2") (pinfunction "2_2") (pintype "passive"))
      (node (ref "U$2") (pin "3") (pinfunction "VCOMH_3") (pintype "bidirectional"))
    )
    (net (code "68") (name "Net-(U$19-FB)") (class "Default")
      (node (ref "C35") (pin "1") (pinfunction "1_1") (pintype "passive"))
      (node (ref "R10") (pin "1") (pinfunction "1_1") (pintype "passive"))
      (node (ref "R7") (pin "2") (pinfunction "2_2") (pintype "passive"))
      (node (ref "U$19") (pin "3") (pinfunction "FB_3") (pintype "bidirectional"))
    )
    (net (code "69") (name "Net-(U$19-SW)") (class "Default")
      (node (ref "D1") (pin "A") (pinfunction "A_A") (pintype "passive"))
      (node (ref "L2") (pin "2") (pinfunction "2_2") (pintype "passive"))
      (node (ref "U$19") (pin "1") (pinfunction "SW_1") (pintype "bidirectional"))
    )
    (net (code "70") (name "Net-(U1-CC1)") (class "Default")
      (node (ref "R4") (pin "1") (pinfunction "1_1") (pintype "passive"))
      (node (ref "U1") (pin "A5") (pinfunction "CC1_A5") (pintype "bidirectional"))
    )
    (net (code "71") (name "Net-(U1-CC2)") (class "Default")
      (node (ref "R3") (pin "1") (pinfunction "1_1") (pintype "passive"))
      (node (ref "U1") (pin "B5") (pinfunction "CC2_B5") (pintype "bidirectional"))
    )
    (net (code "72") (name "Net-(U2-CC1)") (class "Default")
      (node (ref "R9") (pin "1") (pinfunction "1_1") (pintype "passive"))
      (node (ref "U2") (pin "A5") (pinfunction "CC1_A5") (pintype "bidirectional"))
    )
    (net (code "73") (name "Net-(U2-CC2)") (class "Default")
      (node (ref "R1") (pin "1") (pinfunction "1_1") (pintype "passive"))
      (node (ref "U2") (pin "B5") (pinfunction "CC2_B5") (pintype "bidirectional"))
    )
    (net (code "74") (name "Net-(U3-GPIO1)") (class "Default")
      (node (ref "C1") (pin "2") (pinfunction "2_2") (pintype "passive"))
      (node (ref "R8") (pin "1") (pinfunction "1_1") (pintype "passive"))
      (node (ref "U3") (pin "6") (pinfunction "GPIO1_6") (pintype "bidirectional"))
    )
    (net (code "75") (name "Net-(U3-GPIO2)") (class "Default")
      (node (ref "C2") (pin "2") (pinfunction "2_2") (pintype "passive"))
      (node (ref "R13") (pin "1") (pinfunction "1_1") (pintype "passive"))
      (node (ref "U3") (pin "7") (pinfunction "GPIO2_7") (pintype "bidirectional"))
    )
    (net (code "76") (name "Net-(U3-GPIO4)") (class "Default")
      (node (ref "C9") (pin "2") (pinfunction "2_2") (pintype "passive"))
      (node (ref "R14") (pin "1") (pinfunction "1_1") (pintype "passive"))
      (node (ref "U3") (pin "9") (pinfunction "GPIO4_9") (pintype "bidirectional"))
    )
    (net (code "77") (name "Net-(U3-GPIO5)") (class "Default")
      (node (ref "C10") (pin "2") (pinfunction "2_2") (pintype "passive"))
      (node (ref "R15") (pin "1") (pinfunction "1_1") (pintype "passive"))
      (node (ref "U3") (pin "10") (pinfunction "GPIO5_10") (pintype "bidirectional"))
    )
    (net (code "78") (name "Net-(U3-LNA_IN)") (class "Default")
      (node (ref "U3") (pin "1") (pinfunction "LNA_IN_1") (pintype "bidirectional"))
      (node (ref "X1") (pin "3") (pinfunction "SIGNAL_3") (pintype "passive"))
    )
    (net (code "79") (name "Net-(U3-SPICS1)") (class "Default")
      (node (ref "JP1") (pin "1") (pinfunction "1_1") (pintype "passive"))
      (node (ref "U3") (pin "28") (pinfunction "SPICS1_28") (pintype "bidirectional"))
    )
    (net (code "80") (name "Net-(U3-U0TXD)") (class "Default")
      (node (ref "R18") (pin "2") (pinfunction "2_2") (pintype "passive"))
      (node (ref "U3") (pin "49") (pinfunction "U0TXD_49") (pintype "bidirectional"))
    )
    (net (code "81") (name "Net-(U3-XTAL_N)") (class "Default")
      (node (ref "C3") (pin "1") (pinfunction "1_1") (pintype "passive"))
      (node (ref "U3") (pin "53") (pinfunction "XTAL_N_53") (pintype "output"))
      (node (ref "Y1") (pin "3") (pinfunction "2_3") (pintype "passive"))
    )
    (net (code "82") (name "Net-(U3-XTAL_P)") (class "Default")
      (node (ref "C8") (pin "1") (pinfunction "1_1") (pintype "passive"))
      (node (ref "U3") (pin "54") (pinfunction "XTAL_P_54") (pintype "input"))
      (node (ref "Y1") (pin "1") (pinfunction "1_1") (pintype "passive"))
    )
    (net (code "83") (name "unconnected-(JP2-Pad3)") (class "Default")
      (node (ref "JP2") (pin "3") (pinfunction "3_3") (pintype "passive"))
    )
    (net (code "84") (name "unconnected-(LED_R5C1-DO-PadDOUT)") (class "Default")
      (node (ref "LED_R5C1") (pin "DOUT") (pinfunction "DO_DOUT") (pintype "output"))
    )
    (net (code "85") (name "unconnected-(SD1-DAT1-Pad8)") (class "Default")
      (node (ref "SD1") (pin "8") (pinfunction "DAT1_8") (pintype "bidirectional"))
    )
    (net (code "86") (name "unconnected-(SD1-DAT2-Pad1)") (class "Default")
      (node (ref "SD1") (pin "1") (pinfunction "DAT2_1") (pintype "bidirectional"))
    )
    (net (code "87") (name "unconnected-(U1-SBU1-PadA8)") (class "Default")
      (node (ref "U1") (pin "A8") (pinfunction "SBU1_A8") (pintype "bidirectional"))
    )
    (net (code "88") (name "unconnected-(U1-SBU2-PadB8)") (class "Default")
      (node (ref "U1") (pin "B8") (pinfunction "SBU2_B8") (pintype "bidirectional"))
    )
    (net (code "89") (name "unconnected-(U2-SBU1-PadA8)") (class "Default")
      (node (ref "U2") (pin "A8") (pinfunction "SBU1_A8") (pintype "bidirectional"))
    )
    (net (code "90") (name "unconnected-(U2-SBU2-PadB8)") (class "Default")
      (node (ref "U2") (pin "B8") (pinfunction "SBU2_B8") (pintype "bidirectional"))
    )
    (net (code "91") (name "unconnected-(U3-SPICLK-Pad33)") (class "Default")
      (node (ref "U3") (pin "33") (pinfunction "SPICLK_33") (pintype "bidirectional"))
    )
    (net (code "92") (name "unconnected-(U3-SPICS0-Pad32)") (class "Default")
      (node (ref "U3") (pin "32") (pinfunction "SPICS0_32") (pintype "bidirectional"))
    )
    (net (code "93") (name "unconnected-(U3-SPID-Pad35)") (class "Default")
      (node (ref "U3") (pin "35") (pinfunction "SPID_35") (pintype "bidirectional"))
    )
    (net (code "94") (name "unconnected-(U3-SPIHD-Pad30)") (class "Default")
      (node (ref "U3") (pin "30") (pinfunction "SPIHD_30") (pintype "bidirectional"))
    )
    (net (code "95") (name "unconnected-(U3-SPIQ-Pad34)") (class "Default")
      (node (ref "U3") (pin "34") (pinfunction "SPIQ_34") (pintype "bidirectional"))
    )
    (net (code "96") (name "unconnected-(U3-SPIWP-Pad31)") (class "Default")
      (node (ref "U3") (pin "31") (pinfunction "SPIWP_31") (pintype "bidirectional"))
    )
  )
)
